# SCH_6502_copy_2025-03-02.net
KiCad netlist of a schematic drawn in EasyEDA
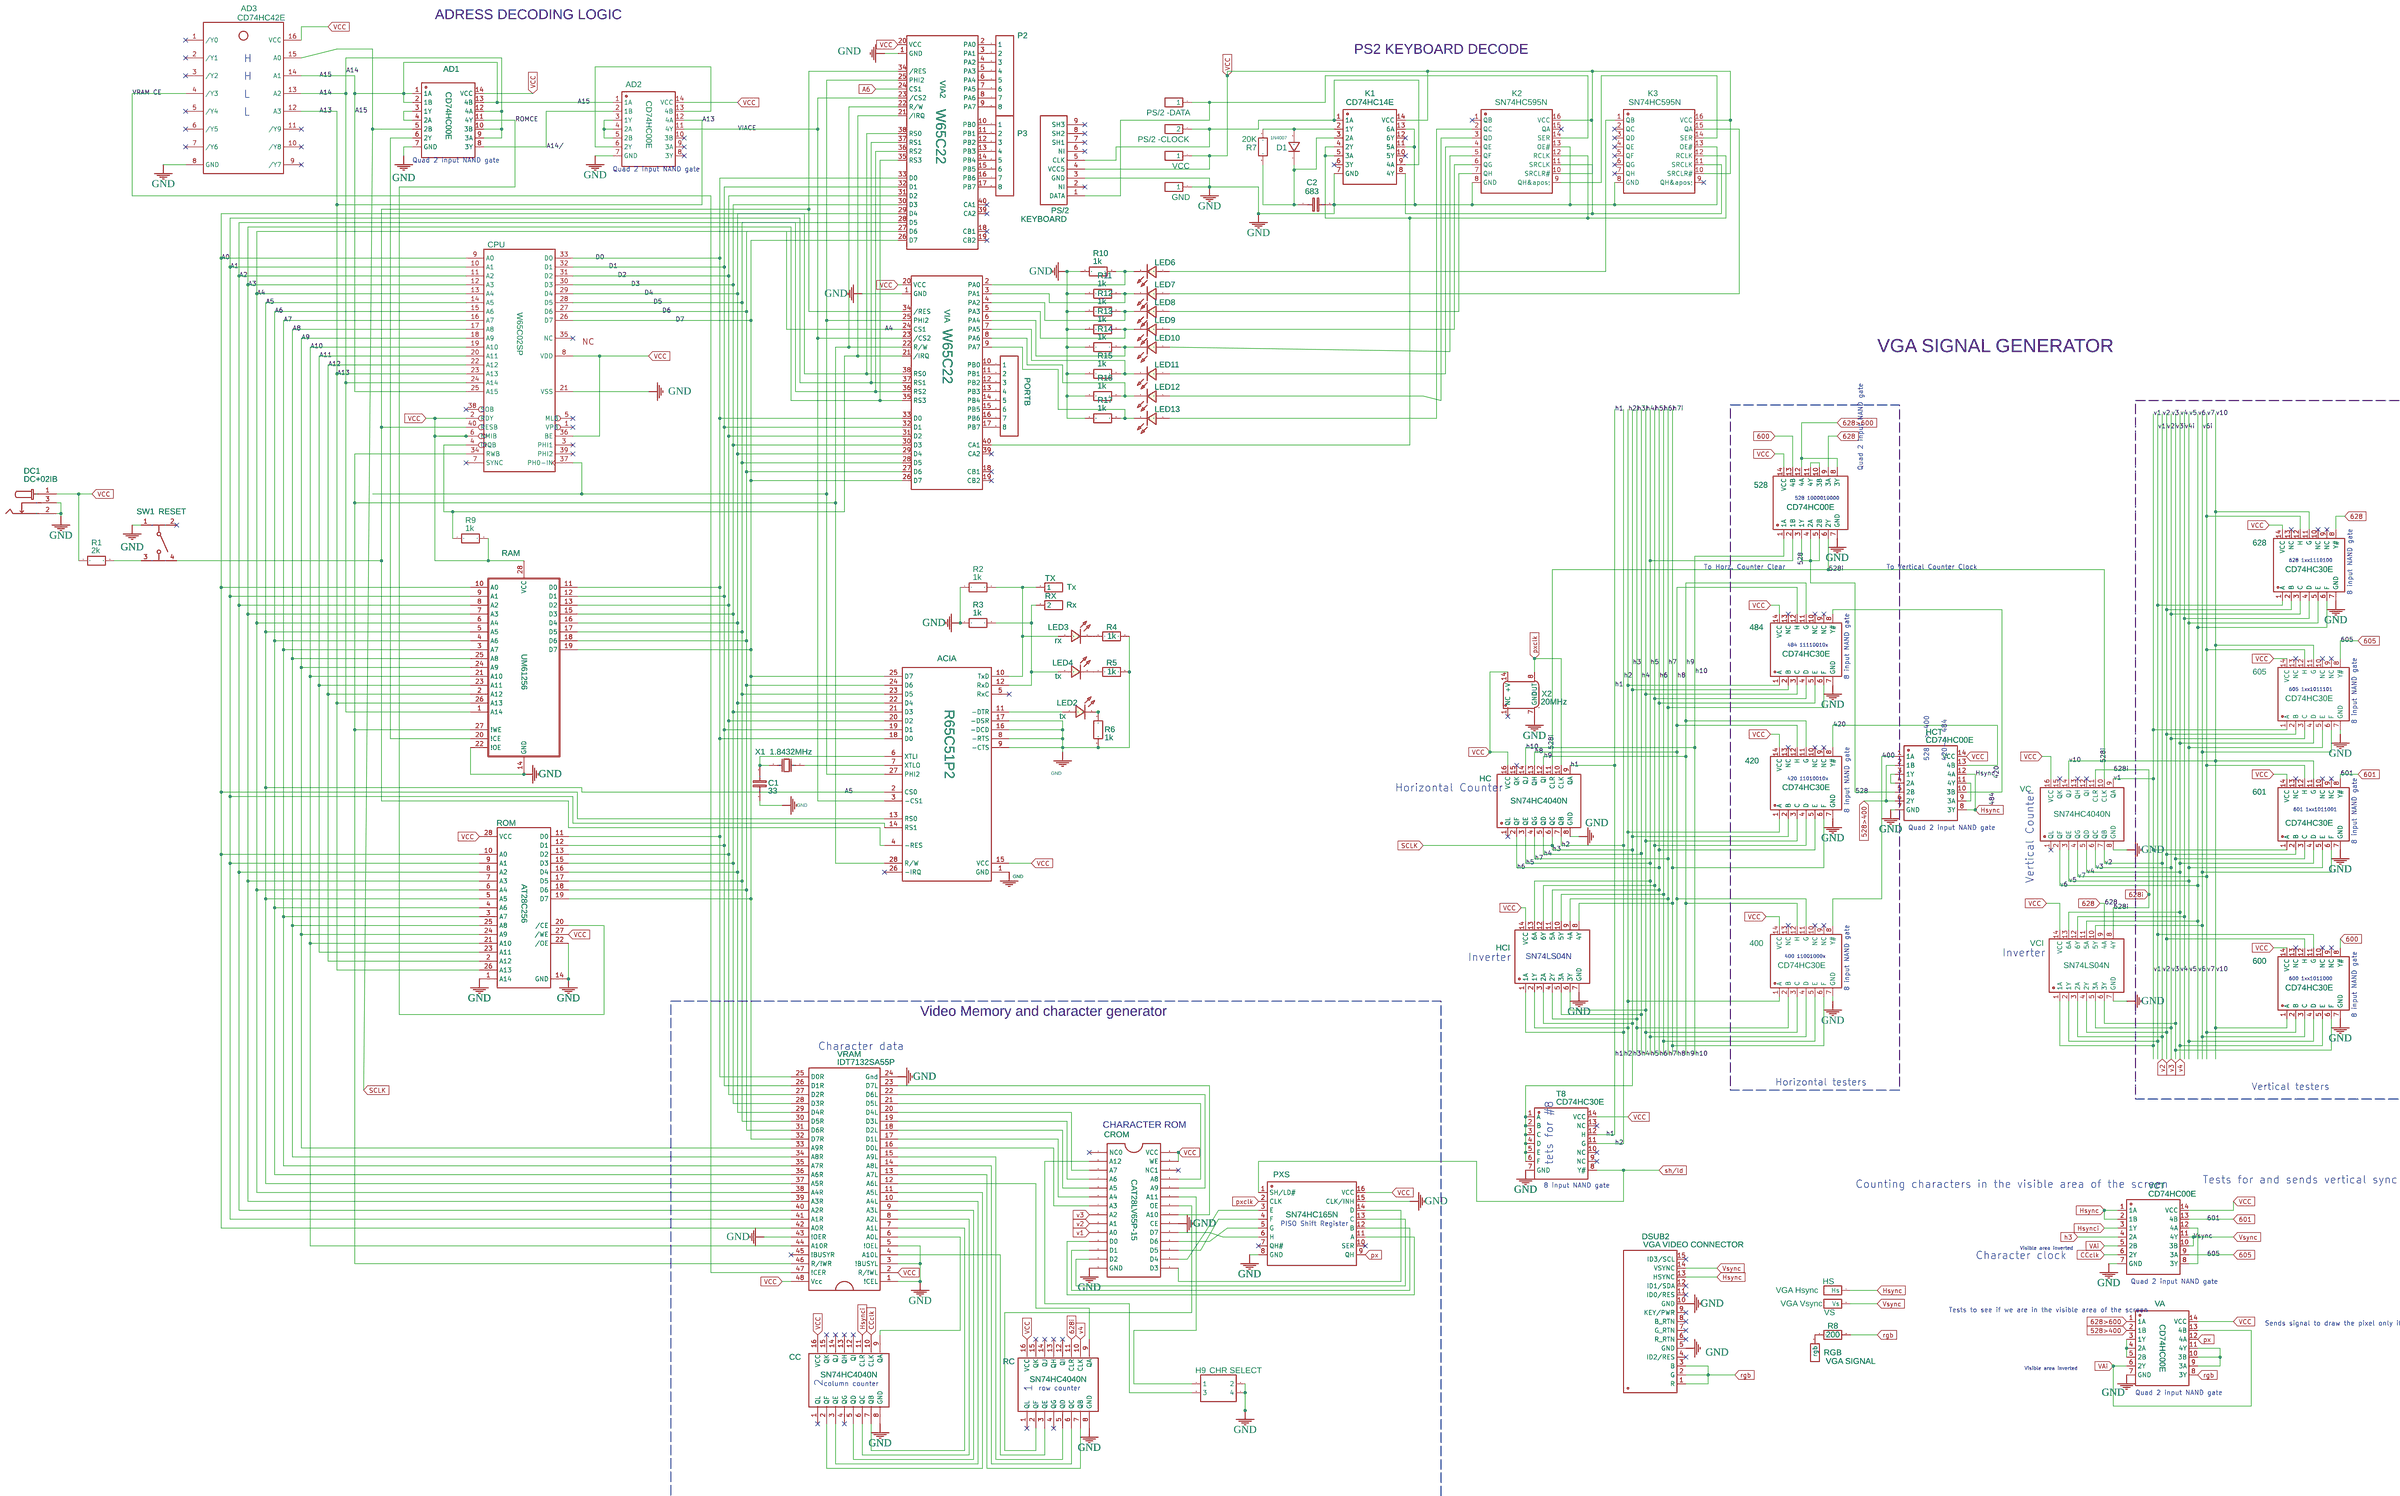
[diagram p0: schematic sheet]

(export (version "E")
  (design (tool "Eeschema 10.0.6"))
  (components
    (comp (ref "400")
      (value "CD74HC30E")
      (fields (field (name "BOM_Supplier Part") "C133818"))
      (libsource (lib "") (part "CD74HC30E"))
    )
    (comp (ref "420")
      (value "CD74HC30E")
      (fields (field (name "BOM_Supplier Part") "C133818"))
      (libsource (lib "") (part "CD74HC30E"))
    )
    (comp (ref "484")
      (value "CD74HC30E")
      (fields (field (name "BOM_Supplier Part") "C133818"))
      (libsource (lib "") (part "CD74HC30E"))
    )
    (comp (ref "528") (value "CD74HC00E") (libsource (lib "") (part "CD74HC00E_1")))
    (comp (ref "600")
      (value "CD74HC30E")
      (fields (field (name "BOM_Supplier Part") "C133818"))
      (libsource (lib "") (part "CD74HC30E"))
    )
    (comp (ref "601")
      (value "CD74HC30E")
      (fields (field (name "BOM_Supplier Part") "C133818"))
      (libsource (lib "") (part "CD74HC30E"))
    )
    (comp (ref "605")
      (value "CD74HC30E")
      (fields (field (name "BOM_Supplier Part") "C133818"))
      (libsource (lib "") (part "CD74HC30E"))
    )
    (comp (ref "628")
      (value "CD74HC30E")
      (fields (field (name "BOM_Supplier Part") "C133818"))
      (libsource (lib "") (part "CD74HC30E"))
    )
    (comp (ref "ACIA")
      (value "R65C51P2")
      (fields (field (name "BOM_Manufacturer Part") "6551 ACIA"))
      (libsource (lib "") (part "R6551_ACIA copy"))
    )
    (comp (ref "AD1") (value "CD74HC00E") (libsource (lib "") (part "CD74HC00E")))
    (comp (ref "AD2") (value "CD74HC00E") (libsource (lib "") (part "CD74HC00E")))
    (comp (ref "AD3") (value "CD74HC42E") (libsource (lib "") (part "CD74HC42E")))
    (comp (ref "C1") (value "33") (libsource (lib "") (part "C_RAD-0.2_EU")))
    (comp (ref "C2") (value "683") (libsource (lib "") (part "C_RAD-0.2_EU_1")))
    (comp (ref "CC") (value "SN74HC4040N") (libsource (lib "") (part "SN74HC4040N_3")))
    (comp (ref "CLK")
      (value "PS/2 -CLOCK")
      (fields (field (name "BOM_Supplier Part") "C81276"))
      (libsource (lib "") (part "HDR-M-2.54_1x1_2"))
    )
    (comp (ref "CPU") (value "W65C02SP") (libsource (lib "") (part "W65C02SP")))
    (comp (ref "CROM")
      (value "CAT28LV65P-15")
      (fields (field (name "BOM_Manufacturer Part") "CAT28C64AP-20"))
      (libsource (lib "") (part "CAT28C64AP-20"))
    )
    (comp (ref "D1")
      (value "1N4007")
      (fields (field (name "BOM_Supplier Part") "C106903"))
      (libsource (lib "") (part "1N4007"))
    )
    (comp (ref "DATA")
      (value "PS/2 -DATA")
      (fields (field (name "BOM_Supplier Part") "C81276"))
      (libsource (lib "") (part "HDR-M-2.54_1x1_4"))
    )
    (comp (ref "DC1")
      (value "DC+02IB")
      (fields (field (name "BOM_Supplier Part") "C718035"))
      (libsource (lib "") (part "DC+02IB"))
    )
    (comp (ref "DSUB2") (value "VGA VIDEO CONNECTOR") (libsource (lib "") (part "VGA VIDEO CONNECTOR")))
    (comp (ref "GND")
      (value "GND")
      (fields (field (name "BOM_Supplier Part") "C81276"))
      (libsource (lib "") (part "HDR-M-2.54_1x1_1"))
    )
    (comp (ref "H9")
      (value "CHR SELECT")
      (fields (field (name "BOM_Supplier Part") "C239342"))
      (libsource (lib "") (part "HDR-F-2.54_2x2"))
    )
    (comp (ref "HC") (value "SN74HC4040N") (libsource (lib "") (part "SN74HC4040N")))
    (comp (ref "HCI")
      (value "U39")
      (fields (field (name "BOM_Manufacturer Part") "SN74LS04N") (field (name "BOM_Supplier Part") "C183657"))
      (libsource (lib "") (part "SN74LS04N"))
    )
    (comp (ref "HCT") (value "CD74HC00E") (libsource (lib "") (part "CD74HC00E_2")))
    (comp (ref "HS")
      (value "VGA Hsync")
      (fields (field (name "BOM_Supplier Part") "C81276"))
      (libsource (lib "") (part "HDR-M-2.54_1x1"))
    )
    (comp (ref "K1") (value "CD74HC14E") (libsource (lib "") (part "CD74HC14E")))
    (comp (ref "K2")
      (value "SN74HC595N")
      (fields (field (name "BOM_Supplier Part") "C78711"))
      (libsource (lib "") (part "SN74HC595N"))
    )
    (comp (ref "K3")
      (value "SN74HC595N")
      (fields (field (name "BOM_Supplier Part") "C78711"))
      (libsource (lib "") (part "SN74HC595N"))
    )
    (comp (ref "KEYBOARD") (value "PS/2") (libsource (lib "") (part "PS/2")))
    (comp (ref "LED2")
      (value "tx")
      (fields
        (field (name "BOM_Manufacturer Part") "204-10SDRD/S530-A3-L")
        (field (name "BOM_Supplier Part") "C84774")
      )
      (libsource (lib "") (part "LED-TH-3mm_R_1"))
    )
    (comp (ref "LED3")
      (value "rx")
      (fields
        (field (name "BOM_Manufacturer Part") "204-10SUBC/S400-A4")
        (field (name "BOM_Supplier Part") "C86881")
      )
      (libsource (lib "") (part "LED-TH-3mm_B"))
    )
    (comp (ref "LED4")
      (value "tx")
      (fields
        (field (name "BOM_Manufacturer Part") "204-10SDRD/S530-A3-L")
        (field (name "BOM_Supplier Part") "C84774")
      )
      (libsource (lib "") (part "LED-TH-3mm_R_1"))
    )
    (comp (ref "LED6")
      (value "LED-TH-3mm_R")
      (fields
        (field (name "BOM_Manufacturer Part") "204-10SDRD/S530-A3-L")
        (field (name "BOM_Supplier Part") "C84774")
      )
      (libsource (lib "") (part "LED-TH-3mm_R"))
    )
    (comp (ref "LED7")
      (value "LED-TH-3mm_R")
      (fields
        (field (name "BOM_Manufacturer Part") "204-10SDRD/S530-A3-L")
        (field (name "BOM_Supplier Part") "C84774")
      )
      (libsource (lib "") (part "LED-TH-3mm_R"))
    )
    (comp (ref "LED8")
      (value "LED-TH-3mm_R")
      (fields
        (field (name "BOM_Manufacturer Part") "204-10SDRD/S530-A3-L")
        (field (name "BOM_Supplier Part") "C84774")
      )
      (libsource (lib "") (part "LED-TH-3mm_R"))
    )
    (comp (ref "LED9")
      (value "LED-TH-3mm_R")
      (fields
        (field (name "BOM_Manufacturer Part") "204-10SDRD/S530-A3-L")
        (field (name "BOM_Supplier Part") "C84774")
      )
      (libsource (lib "") (part "LED-TH-3mm_R"))
    )
    (comp (ref "LED10")
      (value "LED-TH-3mm_R")
      (fields
        (field (name "BOM_Manufacturer Part") "204-10SDRD/S530-A3-L")
        (field (name "BOM_Supplier Part") "C84774")
      )
      (libsource (lib "") (part "LED-TH-3mm_R"))
    )
    (comp (ref "LED11")
      (value "LED-TH-3mm_R")
      (fields
        (field (name "BOM_Manufacturer Part") "204-10SDRD/S530-A3-L")
        (field (name "BOM_Supplier Part") "C84774")
      )
      (libsource (lib "") (part "LED-TH-3mm_R"))
    )
    (comp (ref "LED12")
      (value "LED-TH-3mm_R")
      (fields
        (field (name "BOM_Manufacturer Part") "204-10SDRD/S530-A3-L")
        (field (name "BOM_Supplier Part") "C84774")
      )
      (libsource (lib "") (part "LED-TH-3mm_R"))
    )
    (comp (ref "LED13")
      (value "LED-TH-3mm_R")
      (fields
        (field (name "BOM_Manufacturer Part") "204-10SDRD/S530-A3-L")
        (field (name "BOM_Supplier Part") "C84774")
      )
      (libsource (lib "") (part "LED-TH-3mm_R"))
    )
    (comp (ref "P2")
      (value "HDR-F-2.54_1x8")
      (fields (field (name "BOM_Supplier Part") "C225505"))
      (libsource (lib "") (part "HDR-F-2.54_1x8"))
    )
    (comp (ref "P3")
      (value "P3")
      (fields (field (name "BOM_Supplier Part") "C225505"))
      (libsource (lib "") (part "HDR-F-2.54_1x8"))
    )
    (comp (ref "PORTB")
      (value "HDR-F-2.54_1x8")
      (fields (field (name "BOM_Supplier Part") "C225505"))
      (libsource (lib "") (part "HDR-F-2.54_1x8_1"))
    )
    (comp (ref "PXS")
      (value "SN74HC165N")
      (fields (field (name "BOM_Supplier Part") "C2909"))
      (libsource (lib "") (part "SN74HC165N"))
    )
    (comp (ref "R1") (value "2k") (libsource (lib "") (part "R_AXIAL-0.4_EU")))
    (comp (ref "R2") (value "1k") (libsource (lib "") (part "R_AXIAL-0.3_EU")))
    (comp (ref "R3") (value "1k") (libsource (lib "") (part "R_AXIAL-0.3_EU")))
    (comp (ref "R4") (value "1k") (libsource (lib "") (part "R_AXIAL-0.4_EU")))
    (comp (ref "R5") (value "1k") (libsource (lib "") (part "R_AXIAL-0.4_EU")))
    (comp (ref "R6") (value "1k") (libsource (lib "") (part "R_AXIAL-0.4_EU_1")))
    (comp (ref "R7") (value "20K") (libsource (lib "") (part "R_AXIAL-0.4_EU_1")))
    (comp (ref "R8") (value "200") (libsource (lib "") (part "R_AXIAL-0.4_EU")))
    (comp (ref "R9") (value "1k") (libsource (lib "") (part "R_AXIAL-0.3_EU")))
    (comp (ref "R10") (value "1k") (libsource (lib "") (part "R_AXIAL-0.4_EU")))
    (comp (ref "R11") (value "1k") (libsource (lib "") (part "R_AXIAL-0.4_EU")))
    (comp (ref "R12") (value "1k") (libsource (lib "") (part "R_AXIAL-0.4_EU")))
    (comp (ref "R13") (value "1k") (libsource (lib "") (part "R_AXIAL-0.4_EU")))
    (comp (ref "R14") (value "1k") (libsource (lib "") (part "R_AXIAL-0.4_EU")))
    (comp (ref "R15") (value "1k") (libsource (lib "") (part "R_AXIAL-0.4_EU")))
    (comp (ref "R16") (value "1k") (libsource (lib "") (part "R_AXIAL-0.4_EU")))
    (comp (ref "R17") (value "1k") (libsource (lib "") (part "R_AXIAL-0.4_EU")))
    (comp (ref "RAM") (value "UM61256") (libsource (lib "") (part "UM61256")))
    (comp (ref "RC") (value "SN74HC4040N") (libsource (lib "") (part "SN74HC4040N_2")))
    (comp (ref "RGB")
      (value "VGA SIGNAL")
      (fields (field (name "BOM_Supplier Part") "C81276"))
      (libsource (lib "") (part "HDR-M-2.54_1x1_6"))
    )
    (comp (ref "ROM") (value "AT28C256") (libsource (lib "") (part "AT28C256")))
    (comp (ref "RX")
      (value "Rx")
      (fields (field (name "BOM_Supplier Part") "C81276"))
      (libsource (lib "") (part "HDR-M-2.54_1x1_5"))
    )
    (comp (ref "SW1")
      (value "RESET")
      (fields
        (field (name "BOM_Manufacturer Part") "Switch,6*6*6Plastic head,260G, 0.25mm,Straight line")
        (field (name "BOM_Supplier Part") "C71836")
      )
      (libsource (lib "") (part "Button-6x6x6mm"))
    )
    (comp (ref "T8")
      (value "CD74HC30E")
      (fields (field (name "BOM_Supplier Part") "C133818"))
      (libsource (lib "") (part "CD74HC30E_1"))
    )
    (comp (ref "TX")
      (value "Tx")
      (fields (field (name "BOM_Supplier Part") "C81276"))
      (libsource (lib "") (part "HDR-M-2.54_1x1_8"))
    )
    (comp (ref "VA") (value "CD74HC00E") (libsource (lib "") (part "CD74HC00E_4")))
    (comp (ref "VC") (value "SN74HC4040N") (libsource (lib "") (part "SN74HC4040N_1")))
    (comp (ref "VCC")
      (value "VCC")
      (fields (field (name "BOM_Supplier Part") "C81276"))
      (libsource (lib "") (part "HDR-M-2.54_1x1_7"))
    )
    (comp (ref "VCI")
      (value "SN74LS04N")
      (fields (field (name "BOM_Supplier Part") "C183657"))
      (libsource (lib "") (part "SN74LS04N_1"))
    )
    (comp (ref "VCT") (value "CD74HC00E") (libsource (lib "") (part "CD74HC00E_3")))
    (comp (ref "VIA")
      (value "W65C22")
      (fields (field (name "BOM_Manufacturer Part") "W65C02S"))
      (libsource (lib "") (part "W65C22 VIA"))
    )
    (comp (ref "VIA2")
      (value "W65C22")
      (fields (field (name "BOM_Manufacturer Part") "W65C02S"))
      (libsource (lib "") (part "W65C22 VIA"))
    )
    (comp (ref "VRAM") (value "IDT7132SA55P") (libsource (lib "") (part "IDT7132SA55P")))
    (comp (ref "VS")
      (value "VGA Vsync")
      (fields (field (name "BOM_Supplier Part") "C81276"))
      (libsource (lib "") (part "HDR-M-2.54_1x1_3"))
    )
    (comp (ref "X1")
      (value "1.8432MHz")
      (fields
        (field (name "BOM_Manufacturer Part") "X49UD18432MSD2SC-1")
        (field (name "BOM_Supplier Part") "C2179")
      )
      (libsource (lib "") (part "X49UD18432MSD2SC-1"))
    )
    (comp (ref "X2") (value "20MHz") (libsource (lib "") (part "AXE25-50-10-4F-5.000MHz")))
  )
  (nets
    (net (code "1") (name "/400") (class "Default")
      (node (ref "400") (pin "8") (pinfunction "Y#_8") (pintype "unspecified"))
      (node (ref "HCT") (pin "1") (pinfunction "1A_1") (pintype "unspecified"))
    )
    (net (code "2") (name "/420") (class "Default")
      (node (ref "420") (pin "8") (pinfunction "Y#_8") (pintype "unspecified"))
      (node (ref "HCT") (pin "13") (pinfunction "4B_13") (pintype "unspecified"))
    )
    (net (code "3") (name "/484") (class "Default")
      (node (ref "484") (pin "8") (pinfunction "Y#_8") (pintype "unspecified"))
      (node (ref "HCT") (pin "10") (pinfunction "3B_10") (pintype "unspecified"))
    )
    (net (code "4") (name "/528") (class "Default")
      (node (ref "528") (pin "3") (pinfunction "1Y_3") (pintype "unspecified"))
      (node (ref "528") (pin "4") (pinfunction "2A_4") (pintype "unspecified"))
      (node (ref "528") (pin "5") (pinfunction "2B_5") (pintype "unspecified"))
      (node (ref "HCT") (pin "5") (pinfunction "2B_5") (pintype "unspecified"))
    )
    (net (code "5") (name "/528i") (class "Default")
      (node (ref "528") (pin "6") (pinfunction "2Y_6") (pintype "unspecified"))
      (node (ref "HC") (pin "11") (pinfunction "CLR_11") (pintype "unspecified"))
      (node (ref "VC") (pin "10") (pinfunction "CLK_10") (pintype "unspecified"))
    )
    (net (code "6") (name "/A0") (class "Default")
      (node (ref "ACIA") (pin "13") (pinfunction "RS0_13") (pintype "unspecified"))
      (node (ref "CPU") (pin "9") (pinfunction "A0_9") (pintype "unspecified"))
      (node (ref "RAM") (pin "10") (pinfunction "A0_10") (pintype "input"))
      (node (ref "ROM") (pin "10") (pinfunction "A0_10") (pintype "input"))
      (node (ref "VIA") (pin "38") (pinfunction "RS0_38") (pintype "unspecified"))
      (node (ref "VIA2") (pin "38") (pinfunction "RS0_38") (pintype "unspecified"))
      (node (ref "VRAM") (pin "42") (pinfunction "A0R_42") (pintype "unspecified"))
    )
    (net (code "7") (name "/A1") (class "Default")
      (node (ref "ACIA") (pin "14") (pinfunction "RS1_14") (pintype "unspecified"))
      (node (ref "CPU") (pin "10") (pinfunction "A1_10") (pintype "unspecified"))
      (node (ref "RAM") (pin "9") (pinfunction "A1_9") (pintype "input"))
      (node (ref "ROM") (pin "9") (pinfunction "A1_9") (pintype "input"))
      (node (ref "VIA") (pin "37") (pinfunction "RS1_37") (pintype "unspecified"))
      (node (ref "VIA2") (pin "37") (pinfunction "RS1_37") (pintype "unspecified"))
      (node (ref "VRAM") (pin "41") (pinfunction "A1R_41") (pintype "unspecified"))
    )
    (net (code "8") (name "/A2") (class "Default")
      (node (ref "CPU") (pin "11") (pinfunction "A2_11") (pintype "unspecified"))
      (node (ref "RAM") (pin "8") (pinfunction "A2_8") (pintype "input"))
      (node (ref "ROM") (pin "8") (pinfunction "A2_8") (pintype "input"))
      (node (ref "VIA") (pin "36") (pinfunction "RS2_36") (pintype "unspecified"))
      (node (ref "VIA2") (pin "36") (pinfunction "RS2_36") (pintype "unspecified"))
      (node (ref "VRAM") (pin "40") (pinfunction "A2R_40") (pintype "unspecified"))
    )
    (net (code "9") (name "/A3") (class "Default")
      (node (ref "CPU") (pin "12") (pinfunction "A3_12") (pintype "unspecified"))
      (node (ref "RAM") (pin "7") (pinfunction "A3_7") (pintype "input"))
      (node (ref "ROM") (pin "7") (pinfunction "A3_7") (pintype "input"))
      (node (ref "VIA") (pin "35") (pinfunction "RS3_35") (pintype "unspecified"))
      (node (ref "VIA2") (pin "35") (pinfunction "RS3_35") (pintype "unspecified"))
      (node (ref "VRAM") (pin "39") (pinfunction "A3R_39") (pintype "unspecified"))
    )
    (net (code "10") (name "/A4") (class "Default")
      (node (ref "CPU") (pin "13") (pinfunction "A4_13") (pintype "unspecified"))
      (node (ref "RAM") (pin "6") (pinfunction "A4_6") (pintype "input"))
      (node (ref "ROM") (pin "6") (pinfunction "A4_6") (pintype "input"))
      (node (ref "VIA") (pin "24") (pinfunction "CS1_24") (pintype "unspecified"))
      (node (ref "VRAM") (pin "38") (pinfunction "A4R_38") (pintype "unspecified"))
    )
    (net (code "11") (name "/A5") (class "Default")
      (node (ref "ACIA") (pin "2") (pinfunction "CS0_2") (pintype "unspecified"))
      (node (ref "CPU") (pin "14") (pinfunction "A5_14") (pintype "unspecified"))
      (node (ref "RAM") (pin "5") (pinfunction "A5_5") (pintype "input"))
      (node (ref "ROM") (pin "5") (pinfunction "A5_5") (pintype "input"))
      (node (ref "VRAM") (pin "37") (pinfunction "A5R_37") (pintype "unspecified"))
    )
    (net (code "12") (name "/A7") (class "Default")
      (node (ref "CPU") (pin "16") (pinfunction "A7_16") (pintype "unspecified"))
      (node (ref "RAM") (pin "3") (pinfunction "A7_3") (pintype "input"))
      (node (ref "ROM") (pin "3") (pinfunction "A7_3") (pintype "input"))
      (node (ref "VRAM") (pin "35") (pinfunction "A7R_35") (pintype "unspecified"))
    )
    (net (code "13") (name "/A8") (class "Default")
      (node (ref "CPU") (pin "17") (pinfunction "A8_17") (pintype "unspecified"))
      (node (ref "RAM") (pin "25") (pinfunction "A8_25") (pintype "input"))
      (node (ref "ROM") (pin "25") (pinfunction "A8_25") (pintype "input"))
      (node (ref "VRAM") (pin "34") (pinfunction "A8R_34") (pintype "unspecified"))
    )
    (net (code "14") (name "/A9") (class "Default")
      (node (ref "CPU") (pin "18") (pinfunction "A9_18") (pintype "unspecified"))
      (node (ref "RAM") (pin "24") (pinfunction "A9_24") (pintype "input"))
      (node (ref "ROM") (pin "24") (pinfunction "A9_24") (pintype "input"))
      (node (ref "VRAM") (pin "33") (pinfunction "A9R_33") (pintype "unspecified"))
    )
    (net (code "15") (name "/A10") (class "Default")
      (node (ref "CPU") (pin "19") (pinfunction "A10_19") (pintype "unspecified"))
      (node (ref "RAM") (pin "21") (pinfunction "A10_21") (pintype "input"))
      (node (ref "ROM") (pin "21") (pinfunction "A10_21") (pintype "input"))
      (node (ref "VRAM") (pin "44") (pinfunction "A10R_44") (pintype "unspecified"))
    )
    (net (code "16") (name "/A11") (class "Default")
      (node (ref "CPU") (pin "20") (pinfunction "A11_20") (pintype "unspecified"))
      (node (ref "RAM") (pin "23") (pinfunction "A11_23") (pintype "input"))
      (node (ref "ROM") (pin "23") (pinfunction "A11_23") (pintype "input"))
    )
    (net (code "17") (name "/A12") (class "Default")
      (node (ref "CPU") (pin "22") (pinfunction "A12_22") (pintype "unspecified"))
      (node (ref "RAM") (pin "2") (pinfunction "A12_2") (pintype "input"))
      (node (ref "ROM") (pin "2") (pinfunction "A12_2") (pintype "input"))
    )
    (net (code "18") (name "/A13") (class "Default")
      (node (ref "AD2") (pin "12") (pinfunction "4A_12") (pintype "unspecified"))
      (node (ref "AD3") (pin "12") (pinfunction "A3_12") (pintype "unspecified"))
      (node (ref "CPU") (pin "23") (pinfunction "A13_23") (pintype "unspecified"))
      (node (ref "RAM") (pin "26") (pinfunction "A13_26") (pintype "input"))
      (node (ref "ROM") (pin "26") (pinfunction "A13_26") (pintype "input"))
    )
    (net (code "19") (name "/A14") (class "Default")
      (node (ref "AD1") (pin "10") (pinfunction "3B_10") (pintype "unspecified"))
      (node (ref "AD1") (pin "12") (pinfunction "4A_12") (pintype "unspecified"))
      (node (ref "AD1") (pin "9") (pinfunction "3A_9") (pintype "unspecified"))
      (node (ref "AD3") (pin "13") (pinfunction "A2_13") (pintype "unspecified"))
      (node (ref "CPU") (pin "24") (pinfunction "A14_24") (pintype "unspecified"))
      (node (ref "RAM") (pin "1") (pinfunction "A14_1") (pintype "input"))
    )
    (net (code "20") (name "/A14{slash}") (class "Default")
      (node (ref "AD1") (pin "8") (pinfunction "3Y_8") (pintype "unspecified"))
      (node (ref "AD2") (pin "2") (pinfunction "1B_2") (pintype "unspecified"))
    )
    (net (code "21") (name "/A15") (class "Default")
      (node (ref "AD1") (pin "1") (pinfunction "1A_1") (pintype "unspecified"))
      (node (ref "AD1") (pin "13") (pinfunction "4B_13") (pintype "unspecified"))
      (node (ref "AD1") (pin "2") (pinfunction "1B_2") (pintype "unspecified"))
      (node (ref "AD2") (pin "1") (pinfunction "1A_1") (pintype "unspecified"))
      (node (ref "AD3") (pin "14") (pinfunction "A1_14") (pintype "unspecified"))
      (node (ref "CPU") (pin "25") (pinfunction "A15_25") (pintype "unspecified"))
    )
    (net (code "22") (name "/D0") (class "Default")
      (node (ref "ACIA") (pin "18") (pinfunction "D0_18") (pintype "unspecified"))
      (node (ref "CPU") (pin "33") (pinfunction "D0_33") (pintype "unspecified"))
      (node (ref "RAM") (pin "11") (pinfunction "D0_11") (pintype "unspecified"))
      (node (ref "ROM") (pin "11") (pinfunction "D0_11") (pintype "bidirectional"))
      (node (ref "VIA") (pin "33") (pinfunction "D0_33") (pintype "unspecified"))
      (node (ref "VIA2") (pin "33") (pinfunction "D0_33") (pintype "unspecified"))
      (node (ref "VRAM") (pin "25") (pinfunction "D0R_25") (pintype "unspecified"))
    )
    (net (code "23") (name "/D1") (class "Default")
      (node (ref "ACIA") (pin "19") (pinfunction "D1_19") (pintype "unspecified"))
      (node (ref "CPU") (pin "32") (pinfunction "D1_32") (pintype "unspecified"))
      (node (ref "RAM") (pin "12") (pinfunction "D1_12") (pintype "unspecified"))
      (node (ref "ROM") (pin "12") (pinfunction "D1_12") (pintype "bidirectional"))
      (node (ref "VIA") (pin "32") (pinfunction "D1_32") (pintype "unspecified"))
      (node (ref "VIA2") (pin "32") (pinfunction "D1_32") (pintype "unspecified"))
      (node (ref "VRAM") (pin "26") (pinfunction "D1R_26") (pintype "unspecified"))
    )
    (net (code "24") (name "/D2") (class "Default")
      (node (ref "ACIA") (pin "20") (pinfunction "D2_20") (pintype "unspecified"))
      (node (ref "CPU") (pin "31") (pinfunction "D2_31") (pintype "unspecified"))
      (node (ref "RAM") (pin "13") (pinfunction "D2_13") (pintype "unspecified"))
      (node (ref "ROM") (pin "13") (pinfunction "D2_13") (pintype "bidirectional"))
      (node (ref "VIA") (pin "31") (pinfunction "D2_31") (pintype "unspecified"))
      (node (ref "VIA2") (pin "31") (pinfunction "D2_31") (pintype "unspecified"))
      (node (ref "VRAM") (pin "27") (pinfunction "D2R_27") (pintype "unspecified"))
    )
    (net (code "25") (name "/D3") (class "Default")
      (node (ref "ACIA") (pin "21") (pinfunction "D3_21") (pintype "unspecified"))
      (node (ref "CPU") (pin "30") (pinfunction "D3_30") (pintype "unspecified"))
      (node (ref "RAM") (pin "15") (pinfunction "D3_15") (pintype "unspecified"))
      (node (ref "ROM") (pin "15") (pinfunction "D3_15") (pintype "bidirectional"))
      (node (ref "VIA") (pin "30") (pinfunction "D3_30") (pintype "unspecified"))
      (node (ref "VIA2") (pin "30") (pinfunction "D3_30") (pintype "unspecified"))
      (node (ref "VRAM") (pin "28") (pinfunction "D3R_28") (pintype "unspecified"))
    )
    (net (code "26") (name "/D4") (class "Default")
      (node (ref "ACIA") (pin "22") (pinfunction "D4_22") (pintype "unspecified"))
      (node (ref "CPU") (pin "29") (pinfunction "D4_29") (pintype "unspecified"))
      (node (ref "RAM") (pin "16") (pinfunction "D4_16") (pintype "unspecified"))
      (node (ref "ROM") (pin "16") (pinfunction "D4_16") (pintype "bidirectional"))
      (node (ref "VIA") (pin "29") (pinfunction "D4_29") (pintype "unspecified"))
      (node (ref "VIA2") (pin "29") (pinfunction "D4_29") (pintype "unspecified"))
      (node (ref "VRAM") (pin "29") (pinfunction "D4R_29") (pintype "unspecified"))
    )
    (net (code "27") (name "/D5") (class "Default")
      (node (ref "ACIA") (pin "23") (pinfunction "D5_23") (pintype "unspecified"))
      (node (ref "CPU") (pin "28") (pinfunction "D5_28") (pintype "unspecified"))
      (node (ref "RAM") (pin "17") (pinfunction "D5_17") (pintype "unspecified"))
      (node (ref "ROM") (pin "17") (pinfunction "D5_17") (pintype "bidirectional"))
      (node (ref "VIA") (pin "28") (pinfunction "D5_28") (pintype "unspecified"))
      (node (ref "VIA2") (pin "28") (pinfunction "D5_28") (pintype "unspecified"))
      (node (ref "VRAM") (pin "30") (pinfunction "D5R_30") (pintype "unspecified"))
    )
    (net (code "28") (name "/D6") (class "Default")
      (node (ref "ACIA") (pin "24") (pinfunction "D6_24") (pintype "unspecified"))
      (node (ref "CPU") (pin "27") (pinfunction "D6_27") (pintype "unspecified"))
      (node (ref "RAM") (pin "18") (pinfunction "D6_18") (pintype "unspecified"))
      (node (ref "ROM") (pin "18") (pinfunction "D6_18") (pintype "bidirectional"))
      (node (ref "VIA") (pin "27") (pinfunction "D6_27") (pintype "unspecified"))
      (node (ref "VIA2") (pin "27") (pinfunction "D6_27") (pintype "unspecified"))
      (node (ref "VRAM") (pin "31") (pinfunction "D6R_31") (pintype "unspecified"))
    )
    (net (code "29") (name "/D7") (class "Default")
      (node (ref "ACIA") (pin "25") (pinfunction "D7_25") (pintype "unspecified"))
      (node (ref "CPU") (pin "26") (pinfunction "D7_26") (pintype "unspecified"))
      (node (ref "RAM") (pin "19") (pinfunction "D7_19") (pintype "unspecified"))
      (node (ref "ROM") (pin "19") (pinfunction "D7_19") (pintype "bidirectional"))
      (node (ref "VIA") (pin "26") (pinfunction "D7_26") (pintype "unspecified"))
      (node (ref "VIA2") (pin "26") (pinfunction "D7_26") (pintype "unspecified"))
      (node (ref "VRAM") (pin "32") (pinfunction "D7R_32") (pintype "unspecified"))
    )
    (net (code "30") (name "/ROMCE") (class "Default")
      (node (ref "AD1") (pin "11") (pinfunction "4Y_11") (pintype "unspecified"))
      (node (ref "ROM") (pin "20") (pinfunction "/CE_20") (pintype "input"))
    )
    (net (code "31") (name "/VIACE") (class "Default")
      (node (ref "ACIA") (pin "3") (pinfunction "-CS1_3") (pintype "unspecified"))
      (node (ref "AD2") (pin "11") (pinfunction "4Y_11") (pintype "unspecified"))
      (node (ref "VIA") (pin "23") (pinfunction "/CS2_23") (pintype "unspecified"))
      (node (ref "VIA2") (pin "23") (pinfunction "/CS2_23") (pintype "unspecified"))
    )
    (net (code "32") (name "/VRAM CE") (class "Default")
      (node (ref "AD3") (pin "4") (pinfunction "/Y3_4") (pintype "unspecified"))
      (node (ref "VRAM") (pin "47") (pinfunction "!CER_47") (pintype "unspecified"))
    )
    (net (code "33") (name "/h1") (class "Default")
      (node (ref "HC") (pin "9") (pinfunction "QA_9") (pintype "unspecified"))
      (node (ref "T8") (pin "12") (pinfunction "H_12") (pintype "unspecified"))
    )
    (net (code "34") (name "/h2") (class "Default")
      (node (ref "HC") (pin "7") (pinfunction "QB_7") (pintype "unspecified"))
      (node (ref "HCI") (pin "1") (pinfunction "1A_1") (pintype "unspecified"))
      (node (ref "T8") (pin "11") (pinfunction "G_11") (pintype "unspecified"))
    )
    (net (code "35") (name "/h2i") (class "Default")
      (node (ref "400") (pin "1") (pinfunction "A_1") (pintype "unspecified"))
      (node (ref "420") (pin "1") (pinfunction "A_1") (pintype "unspecified"))
      (node (ref "484") (pin "1") (pinfunction "A_1") (pintype "unspecified"))
      (node (ref "HCI") (pin "2") (pinfunction "1Y_2") (pintype "unspecified"))
    )
    (net (code "36") (name "/h3i") (class "Default")
      (node (ref "400") (pin "2") (pinfunction "B_2") (pintype "unspecified"))
      (node (ref "HCI") (pin "4") (pinfunction "2Y_4") (pintype "unspecified"))
    )
    (net (code "37") (name "/h4") (class "Default")
      (node (ref "HC") (pin "5") (pinfunction "QD_5") (pintype "unspecified"))
      (node (ref "HCI") (pin "5") (pinfunction "3A_5") (pintype "unspecified"))
    )
    (net (code "38") (name "/h4i") (class "Default")
      (node (ref "400") (pin "3") (pinfunction "C_3") (pintype "unspecified"))
      (node (ref "420") (pin "3") (pinfunction "C_3") (pintype "unspecified"))
      (node (ref "484") (pin "3") (pinfunction "C_3") (pintype "unspecified"))
      (node (ref "HCI") (pin "6") (pinfunction "3Y_6") (pintype "unspecified"))
    )
    (net (code "39") (name "/h5") (class "Default")
      (node (ref "400") (pin "4") (pinfunction "D_4") (pintype "unspecified"))
      (node (ref "528") (pin "2") (pinfunction "1B_2") (pintype "unspecified"))
      (node (ref "HC") (pin "3") (pinfunction "QE_3") (pintype "unspecified"))
      (node (ref "HCI") (pin "13") (pinfunction "6A_13") (pintype "unspecified"))
    )
    (net (code "40") (name "/h5i") (class "Default")
      (node (ref "420") (pin "4") (pinfunction "D_4") (pintype "unspecified"))
      (node (ref "484") (pin "4") (pinfunction "D_4") (pintype "unspecified"))
      (node (ref "HCI") (pin "12") (pinfunction "6Y_12") (pintype "unspecified"))
    )
    (net (code "41") (name "/h6") (class "Default")
      (node (ref "420") (pin "5") (pinfunction "E_5") (pintype "unspecified"))
      (node (ref "484") (pin "5") (pinfunction "E_5") (pintype "unspecified"))
      (node (ref "HC") (pin "2") (pinfunction "QF_2") (pintype "unspecified"))
      (node (ref "HCI") (pin "11") (pinfunction "5A_11") (pintype "unspecified"))
    )
    (net (code "42") (name "/h6i") (class "Default")
      (node (ref "400") (pin "5") (pinfunction "E_5") (pintype "unspecified"))
      (node (ref "HCI") (pin "10") (pinfunction "5Y_10") (pintype "unspecified"))
    )
    (net (code "43") (name "/h7") (class "Default")
      (node (ref "484") (pin "6") (pinfunction "F_6") (pintype "unspecified"))
      (node (ref "HC") (pin "4") (pinfunction "QG_4") (pintype "unspecified"))
      (node (ref "HCI") (pin "9") (pinfunction "4A_9") (pintype "unspecified"))
    )
    (net (code "44") (name "/h7i") (class "Default")
      (node (ref "400") (pin "6") (pinfunction "F_6") (pintype "unspecified"))
      (node (ref "420") (pin "6") (pinfunction "F_6") (pintype "unspecified"))
      (node (ref "HCI") (pin "8") (pinfunction "4Y_8") (pintype "unspecified"))
    )
    (net (code "45") (name "/h8") (class "Default")
      (node (ref "400") (pin "11") (pinfunction "G_11") (pintype "unspecified"))
      (node (ref "420") (pin "12") (pinfunction "H_12") (pintype "unspecified"))
      (node (ref "484") (pin "12") (pinfunction "H_12") (pintype "unspecified"))
      (node (ref "HC") (pin "13") (pinfunction "QH_13") (pintype "unspecified"))
    )
    (net (code "46") (name "/h9") (class "Default")
      (node (ref "400") (pin "12") (pinfunction "H_12") (pintype "unspecified"))
      (node (ref "420") (pin "11") (pinfunction "G_11") (pintype "unspecified"))
      (node (ref "484") (pin "11") (pinfunction "G_11") (pintype "unspecified"))
      (node (ref "HC") (pin "12") (pinfunction "QI_12") (pintype "unspecified"))
    )
    (net (code "47") (name "/h10") (class "Default")
      (node (ref "528") (pin "1") (pinfunction "1A_1") (pintype "unspecified"))
      (node (ref "HC") (pin "14") (pinfunction "QJ_14") (pintype "unspecified"))
    )
    (net (code "48") (name "/v1i") (class "Default")
      (node (ref "600") (pin "11") (pinfunction "G_11") (pintype "unspecified"))
      (node (ref "628") (pin "1") (pinfunction "A_1") (pintype "unspecified"))
      (node (ref "VCI") (pin "2") (pinfunction "1Y_2") (pintype "unspecified"))
    )
    (net (code "49") (name "/v2i") (class "Default")
      (node (ref "600") (pin "12") (pinfunction "H_12") (pintype "unspecified"))
      (node (ref "601") (pin "2") (pinfunction "B_2") (pintype "unspecified"))
      (node (ref "605") (pin "2") (pinfunction "B_2") (pintype "unspecified"))
      (node (ref "628") (pin "2") (pinfunction "B_2") (pintype "unspecified"))
      (node (ref "VCI") (pin "4") (pinfunction "2Y_4") (pintype "unspecified"))
    )
    (net (code "50") (name "/v3i") (class "Default")
      (node (ref "600") (pin "6") (pinfunction "F_6") (pintype "unspecified"))
      (node (ref "601") (pin "3") (pinfunction "C_3") (pintype "unspecified"))
      (node (ref "VCI") (pin "6") (pinfunction "3Y_6") (pintype "unspecified"))
    )
    (net (code "51") (name "/v4i") (class "Default")
      (node (ref "628") (pin "4") (pinfunction "D_4") (pintype "unspecified"))
      (node (ref "VCI") (pin "12") (pinfunction "6Y_12") (pintype "unspecified"))
    )
    (net (code "52") (name "/v5") (class "Default")
      (node (ref "600") (pin "4") (pinfunction "D_4") (pintype "unspecified"))
      (node (ref "601") (pin "5") (pinfunction "E_5") (pintype "unspecified"))
      (node (ref "605") (pin "5") (pinfunction "E_5") (pintype "unspecified"))
      (node (ref "628") (pin "5") (pinfunction "E_5") (pintype "unspecified"))
      (node (ref "VC") (pin "3") (pinfunction "QE_3") (pintype "unspecified"))
    )
    (net (code "53") (name "/v6") (class "Default")
      (node (ref "628") (pin "6") (pinfunction "F_6") (pintype "unspecified"))
      (node (ref "VC") (pin "2") (pinfunction "QF_2") (pintype "unspecified"))
      (node (ref "VCI") (pin "11") (pinfunction "5A_11") (pintype "unspecified"))
    )
    (net (code "54") (name "/v6i") (class "Default")
      (node (ref "600") (pin "3") (pinfunction "C_3") (pintype "unspecified"))
      (node (ref "601") (pin "6") (pinfunction "F_6") (pintype "unspecified"))
      (node (ref "605") (pin "6") (pinfunction "F_6") (pintype "unspecified"))
      (node (ref "VCI") (pin "10") (pinfunction "5Y_10") (pintype "unspecified"))
    )
    (net (code "55") (name "/v7") (class "Default")
      (node (ref "600") (pin "2") (pinfunction "B_2") (pintype "unspecified"))
      (node (ref "601") (pin "12") (pinfunction "H_12") (pintype "unspecified"))
      (node (ref "605") (pin "12") (pinfunction "H_12") (pintype "unspecified"))
      (node (ref "628") (pin "12") (pinfunction "H_12") (pintype "unspecified"))
      (node (ref "VC") (pin "4") (pinfunction "QG_4") (pintype "unspecified"))
    )
    (net (code "56") (name "/v10") (class "Default")
      (node (ref "600") (pin "1") (pinfunction "A_1") (pintype "unspecified"))
      (node (ref "601") (pin "11") (pinfunction "G_11") (pintype "unspecified"))
      (node (ref "605") (pin "11") (pinfunction "G_11") (pintype "unspecified"))
      (node (ref "628") (pin "11") (pinfunction "G_11") (pintype "unspecified"))
      (node (ref "VC") (pin "14") (pinfunction "QJ_14") (pintype "unspecified"))
    )
    (net (code "57") (name "528>400") (class "Default")
      (node (ref "HCT") (pin "2") (pinfunction "1B_2") (pintype "unspecified"))
      (node (ref "HCT") (pin "6") (pinfunction "2Y_6") (pintype "unspecified"))
      (node (ref "VA") (pin "2") (pinfunction "1B_2") (pintype "unspecified"))
    )
    (net (code "58") (name "600") (class "Default")
      (node (ref "528") (pin "13") (pinfunction "4B_13") (pintype "unspecified"))
      (node (ref "600") (pin "8") (pinfunction "Y#_8") (pintype "unspecified"))
    )
    (net (code "59") (name "601") (class "Default")
      (node (ref "601") (pin "8") (pinfunction "Y#_8") (pintype "unspecified"))
      (node (ref "VCT") (pin "13") (pinfunction "4B_13") (pintype "unspecified"))
    )
    (net (code "60") (name "605") (class "Default")
      (node (ref "605") (pin "8") (pinfunction "Y#_8") (pintype "unspecified"))
      (node (ref "VCT") (pin "9") (pinfunction "3A_9") (pintype "unspecified"))
    )
    (net (code "61") (name "628") (class "Default")
      (node (ref "528") (pin "9") (pinfunction "3A_9") (pintype "unspecified"))
      (node (ref "628") (pin "8") (pinfunction "Y#_8") (pintype "unspecified"))
      (node (ref "VCI") (pin "9") (pinfunction "4A_9") (pintype "unspecified"))
    )
    (net (code "62") (name "628>600") (class "Default")
      (node (ref "528") (pin "12") (pinfunction "4A_12") (pintype "unspecified"))
      (node (ref "528") (pin "8") (pinfunction "3Y_8") (pintype "unspecified"))
      (node (ref "VA") (pin "1") (pinfunction "1A_1") (pintype "unspecified"))
    )
    (net (code "63") (name "628i") (class "Default")
      (node (ref "RC") (pin "11") (pinfunction "CLR_11") (pintype "bidirectional"))
      (node (ref "VC") (pin "11") (pinfunction "CLR_11") (pintype "unspecified"))
      (node (ref "VCI") (pin "8") (pinfunction "4Y_8") (pintype "unspecified"))
    )
    (net (code "64") (name "A6") (class "Default")
      (node (ref "CPU") (pin "15") (pinfunction "A6_15") (pintype "unspecified"))
      (node (ref "RAM") (pin "4") (pinfunction "A6_4") (pintype "input"))
      (node (ref "ROM") (pin "4") (pinfunction "A6_4") (pintype "input"))
      (node (ref "VIA2") (pin "24") (pinfunction "CS1_24") (pintype "unspecified"))
      (node (ref "VRAM") (pin "36") (pinfunction "A6R_36") (pintype "unspecified"))
    )
    (net (code "65") (name "CCclk") (class "Default")
      (node (ref "CC") (pin "10") (pinfunction "CLK_10") (pintype "bidirectional"))
      (node (ref "VCT") (pin "6") (pinfunction "2Y_6") (pintype "unspecified"))
    )
    (net (code "66") (name "GND") (class "Default")
      (node (ref "400") (pin "7") (pinfunction "GND_7") (pintype "unspecified"))
      (node (ref "420") (pin "7") (pinfunction "GND_7") (pintype "unspecified"))
      (node (ref "484") (pin "7") (pinfunction "GND_7") (pintype "unspecified"))
      (node (ref "528") (pin "7") (pinfunction "GND_7") (pintype "unspecified"))
      (node (ref "600") (pin "7") (pinfunction "GND_7") (pintype "unspecified"))
      (node (ref "601") (pin "7") (pinfunction "GND_7") (pintype "unspecified"))
      (node (ref "605") (pin "7") (pinfunction "GND_7") (pintype "unspecified"))
      (node (ref "628") (pin "7") (pinfunction "GND_7") (pintype "unspecified"))
      (node (ref "ACIA") (pin "1") (pinfunction "GND_1") (pintype "unspecified"))
      (node (ref "ACIA") (pin "16") (pinfunction "-DCD_16") (pintype "unspecified"))
      (node (ref "ACIA") (pin "17") (pinfunction "-DSR_17") (pintype "unspecified"))
      (node (ref "ACIA") (pin "8") (pinfunction "-RTS_8") (pintype "unspecified"))
      (node (ref "ACIA") (pin "9") (pinfunction "-CTS_9") (pintype "unspecified"))
      (node (ref "AD1") (pin "7") (pinfunction "GND_7") (pintype "unspecified"))
      (node (ref "AD2") (pin "7") (pinfunction "GND_7") (pintype "unspecified"))
      (node (ref "AD3") (pin "8") (pinfunction "GND_8") (pintype "unspecified"))
      (node (ref "C1") (pin "1") (pinfunction "1_1") (pintype "unspecified"))
      (node (ref "C2") (pin "2") (pinfunction "2_2") (pintype "unspecified"))
      (node (ref "CC") (pin "8") (pinfunction "GND_8") (pintype "bidirectional"))
      (node (ref "CPU") (pin "21") (pinfunction "VSS_21") (pintype "unspecified"))
      (node (ref "CROM") (pin "14") (pinfunction "GND_14") (pintype "unspecified"))
      (node (ref "CROM") (pin "20") (pinfunction "CE_20") (pintype "unspecified"))
      (node (ref "DC1") (pin "2") (pinfunction "2_2") (pintype "unspecified"))
      (node (ref "DC1") (pin "3") (pinfunction "3_3") (pintype "unspecified"))
      (node (ref "DSUB2") (pin "10") (pinfunction "GND_10") (pintype "unspecified"))
      (node (ref "DSUB2") (pin "5") (pinfunction "GND_5") (pintype "unspecified"))
      (node (ref "GND") (pin "1") (pinfunction "1_1") (pintype "input"))
      (node (ref "H9") (pin "2") (pinfunction "2_2") (pintype "unspecified"))
      (node (ref "H9") (pin "4") (pinfunction "4_4") (pintype "unspecified"))
      (node (ref "HC") (pin "8") (pinfunction "GND_8") (pintype "unspecified"))
      (node (ref "HCI") (pin "7") (pinfunction "GND_7") (pintype "unspecified"))
      (node (ref "HCT") (pin "7") (pinfunction "GND_7") (pintype "unspecified"))
      (node (ref "K1") (pin "11") (pinfunction "5A_11") (pintype "unspecified"))
      (node (ref "K1") (pin "13") (pinfunction "6A_13") (pintype "unspecified"))
      (node (ref "K1") (pin "7") (pinfunction "GND_7") (pintype "unspecified"))
      (node (ref "K2") (pin "13") (pinfunction "OE#_13") (pintype "unspecified"))
      (node (ref "K2") (pin "8") (pinfunction "GND_8") (pintype "unspecified"))
      (node (ref "K3") (pin "13") (pinfunction "OE#_13") (pintype "unspecified"))
      (node (ref "K3") (pin "8") (pinfunction "GND_8") (pintype "unspecified"))
      (node (ref "KEYBOARD") (pin "3") (pinfunction "GND_3") (pintype "passive"))
      (node (ref "PXS") (pin "15") (pinfunction "CLK/INH_15") (pintype "unspecified"))
      (node (ref "PXS") (pin "8") (pinfunction "GND_8") (pintype "unspecified"))
      (node (ref "R10") (pin "1") (pinfunction "1_1") (pintype "unspecified"))
      (node (ref "R11") (pin "1") (pinfunction "1_1") (pintype "unspecified"))
      (node (ref "R12") (pin "1") (pinfunction "1_1") (pintype "unspecified"))
      (node (ref "R13") (pin "1") (pinfunction "1_1") (pintype "unspecified"))
      (node (ref "R14") (pin "1") (pinfunction "1_1") (pintype "unspecified"))
      (node (ref "R15") (pin "1") (pinfunction "1_1") (pintype "unspecified"))
      (node (ref "R16") (pin "1") (pinfunction "1_1") (pintype "unspecified"))
      (node (ref "R17") (pin "1") (pinfunction "1_1") (pintype "unspecified"))
      (node (ref "R2") (pin "1") (pinfunction "1_1") (pintype "unspecified"))
      (node (ref "R3") (pin "1") (pinfunction "1_1") (pintype "unspecified"))
      (node (ref "R4") (pin "2") (pinfunction "2_2") (pintype "unspecified"))
      (node (ref "R5") (pin "2") (pinfunction "2_2") (pintype "unspecified"))
      (node (ref "R6") (pin "2") (pinfunction "2_2") (pintype "unspecified"))
      (node (ref "RAM") (pin "14") (pinfunction "GND_14") (pintype "unspecified"))
      (node (ref "RAM") (pin "22") (pinfunction "!OE_22") (pintype "input"))
      (node (ref "RC") (pin "8") (pinfunction "GND_8") (pintype "bidirectional"))
      (node (ref "ROM") (pin "1") (pinfunction "A14_1") (pintype "input"))
      (node (ref "ROM") (pin "14") (pinfunction "GND_14") (pintype "passive"))
      (node (ref "ROM") (pin "22") (pinfunction "/OE_22") (pintype "input"))
      (node (ref "SW1") (pin "1") (pinfunction "1_1") (pintype "unspecified"))
      (node (ref "T8") (pin "7") (pinfunction "GND_7") (pintype "unspecified"))
      (node (ref "VA") (pin "7") (pinfunction "GND_7") (pintype "unspecified"))
      (node (ref "VC") (pin "8") (pinfunction "GND_8") (pintype "unspecified"))
      (node (ref "VCI") (pin "7") (pinfunction "GND_7") (pintype "unspecified"))
      (node (ref "VCT") (pin "7") (pinfunction "GND_7") (pintype "unspecified"))
      (node (ref "VIA") (pin "1") (pinfunction "GND_1") (pintype "unspecified"))
      (node (ref "VIA2") (pin "1") (pinfunction "GND_1") (pintype "unspecified"))
      (node (ref "VRAM") (pin "1") (pinfunction "!CEL_1") (pintype "unspecified"))
      (node (ref "VRAM") (pin "24") (pinfunction "Gnd_24") (pintype "unspecified"))
      (node (ref "VRAM") (pin "3") (pinfunction "!BUSYL_3") (pintype "unspecified"))
      (node (ref "VRAM") (pin "43") (pinfunction "!OER_43") (pintype "unspecified"))
      (node (ref "VRAM") (pin "5") (pinfunction "!OEL_5") (pintype "unspecified"))
      (node (ref "X2") (pin "7") (pinfunction "GND_7") (pintype "unspecified"))
    )
    (net (code "67") (name "Hsync") (class "Default")
      (node (ref "DSUB2") (pin "13") (pinfunction "HSYNC_13") (pintype "unspecified"))
      (node (ref "HCT") (pin "12") (pinfunction "4A_12") (pintype "unspecified"))
      (node (ref "HCT") (pin "8") (pinfunction "3Y_8") (pintype "unspecified"))
      (node (ref "HS") (pin "1") (pinfunction "Hs_1") (pintype "input"))
      (node (ref "VCT") (pin "1") (pinfunction "1A_1") (pintype "unspecified"))
      (node (ref "VCT") (pin "2") (pinfunction "1B_2") (pintype "unspecified"))
    )
    (net (code "68") (name "Hsynci") (class "Default")
      (node (ref "CC") (pin "11") (pinfunction "CLR_11") (pintype "bidirectional"))
      (node (ref "VCT") (pin "3") (pinfunction "1Y_3") (pintype "unspecified"))
    )
    (net (code "69") (name "Net-(528-3B)") (class "Default")
      (node (ref "528") (pin "10") (pinfunction "3B_10") (pintype "unspecified"))
      (node (ref "528") (pin "11") (pinfunction "4Y_11") (pintype "unspecified"))
    )
    (net (code "70") (name "Net-(ACIA--DTR)") (class "Default")
      (node (ref "ACIA") (pin "11") (pinfunction "-DTR_11") (pintype "unspecified"))
      (node (ref "LED2") (pin "1") (pinfunction "1_1") (pintype "unspecified"))
    )
    (net (code "71") (name "Net-(ACIA--RES)") (class "Default")
      (node (ref "ACIA") (pin "4") (pinfunction "-RES_4") (pintype "unspecified"))
      (node (ref "CPU") (pin "40") (pinfunction "RESB_40") (pintype "input"))
      (node (ref "SW1") (pin "4") (pinfunction "4_4") (pintype "unspecified"))
      (node (ref "VIA") (pin "34") (pinfunction "/RES_34") (pintype "unspecified"))
      (node (ref "VIA2") (pin "34") (pinfunction "/RES_34") (pintype "unspecified"))
    )
    (net (code "72") (name "Net-(ACIA-PHI2)") (class "Default")
      (node (ref "ACIA") (pin "27") (pinfunction "PHI2_27") (pintype "unspecified"))
      (node (ref "CPU") (pin "37") (pinfunction "PH0-IN_37") (pintype "input"))
      (node (ref "VIA") (pin "25") (pinfunction "PHI2_25") (pintype "unspecified"))
      (node (ref "VIA2") (pin "25") (pinfunction "PHI2_25") (pintype "unspecified"))
    )
    (net (code "73") (name "Net-(ACIA-RxD)") (class "Default")
      (node (ref "ACIA") (pin "12") (pinfunction "RxD_12") (pintype "unspecified"))
      (node (ref "LED4") (pin "1") (pinfunction "1_1") (pintype "unspecified"))
      (node (ref "R3") (pin "2") (pinfunction "2_2") (pintype "unspecified"))
      (node (ref "RX") (pin "1") (pinfunction "2_1") (pintype "input"))
    )
    (net (code "74") (name "Net-(ACIA-R{slash}W)") (class "Default")
      (node (ref "ACIA") (pin "28") (pinfunction "R/W_28") (pintype "unspecified"))
      (node (ref "CPU") (pin "34") (pinfunction "RWB_34") (pintype "output"))
      (node (ref "RAM") (pin "27") (pinfunction "!WE_27") (pintype "input"))
      (node (ref "VIA") (pin "22") (pinfunction "R/W_22") (pintype "unspecified"))
      (node (ref "VIA2") (pin "22") (pinfunction "R/W_22") (pintype "unspecified"))
      (node (ref "VRAM") (pin "46") (pinfunction "R/!WR_46") (pintype "unspecified"))
    )
    (net (code "75") (name "Net-(ACIA-TxD)") (class "Default")
      (node (ref "ACIA") (pin "10") (pinfunction "TxD_10") (pintype "unspecified"))
      (node (ref "LED3") (pin "1") (pinfunction "1_1") (pintype "unspecified"))
      (node (ref "R2") (pin "2") (pinfunction "2_2") (pintype "unspecified"))
      (node (ref "TX") (pin "1") (pinfunction "1_1") (pintype "input"))
    )
    (net (code "76") (name "Net-(ACIA-XTLI)") (class "Default")
      (node (ref "ACIA") (pin "6") (pinfunction "XTLI_6") (pintype "unspecified"))
      (node (ref "C1") (pin "2") (pinfunction "2_2") (pintype "unspecified"))
      (node (ref "X1") (pin "2") (pinfunction "OSC2_2") (pintype "input"))
    )
    (net (code "77") (name "Net-(ACIA-XTLO)") (class "Default")
      (node (ref "ACIA") (pin "7") (pinfunction "XTLO_7") (pintype "unspecified"))
      (node (ref "X1") (pin "1") (pinfunction "OSC1_1") (pintype "input"))
    )
    (net (code "78") (name "Net-(AD1-1Y)") (class "Default")
      (node (ref "AD1") (pin "3") (pinfunction "1Y_3") (pintype "unspecified"))
      (node (ref "AD1") (pin "4") (pinfunction "2A_4") (pintype "unspecified"))
    )
    (net (code "79") (name "Net-(AD1-2Y)") (class "Default")
      (node (ref "AD1") (pin "6") (pinfunction "2Y_6") (pintype "unspecified"))
      (node (ref "RAM") (pin "20") (pinfunction "!CE_20") (pintype "input"))
    )
    (net (code "80") (name "Net-(AD2-1Y)") (class "Default")
      (node (ref "AD2") (pin "3") (pinfunction "1Y_3") (pintype "unspecified"))
      (node (ref "AD2") (pin "4") (pinfunction "2A_4") (pintype "unspecified"))
      (node (ref "AD2") (pin "5") (pinfunction "2B_5") (pintype "unspecified"))
    )
    (net (code "81") (name "Net-(AD2-2Y)") (class "Default")
      (node (ref "AD2") (pin "13") (pinfunction "4B_13") (pintype "unspecified"))
      (node (ref "AD2") (pin "6") (pinfunction "2Y_6") (pintype "unspecified"))
    )
    (net (code "82") (name "Net-(CC-QA)") (class "Default")
      (node (ref "CC") (pin "9") (pinfunction "QA_9") (pintype "bidirectional"))
      (node (ref "VRAM") (pin "6") (pinfunction "A0L_6") (pintype "unspecified"))
    )
    (net (code "83") (name "Net-(CC-QB)") (class "Default")
      (node (ref "CC") (pin "7") (pinfunction "QB_7") (pintype "bidirectional"))
      (node (ref "VRAM") (pin "7") (pinfunction "A1L_7") (pintype "unspecified"))
    )
    (net (code "84") (name "Net-(CC-QC)") (class "Default")
      (node (ref "CC") (pin "6") (pinfunction "QC_6") (pintype "bidirectional"))
      (node (ref "VRAM") (pin "8") (pinfunction "A2L_8") (pintype "unspecified"))
    )
    (net (code "85") (name "Net-(CC-QD)") (class "Default")
      (node (ref "CC") (pin "5") (pinfunction "QD_5") (pintype "bidirectional"))
      (node (ref "VRAM") (pin "9") (pinfunction "A3L_9") (pintype "unspecified"))
    )
    (net (code "86") (name "Net-(CC-QE)") (class "Default")
      (node (ref "CC") (pin "3") (pinfunction "QE_3") (pintype "bidirectional"))
      (node (ref "VRAM") (pin "10") (pinfunction "A4L_10") (pintype "unspecified"))
    )
    (net (code "87") (name "Net-(CC-QF)") (class "Default")
      (node (ref "CC") (pin "2") (pinfunction "QF_2") (pintype "bidirectional"))
      (node (ref "VRAM") (pin "11") (pinfunction "A5L_11") (pintype "unspecified"))
    )
    (net (code "88") (name "Net-(CLK-2)") (class "Default")
      (node (ref "CLK") (pin "1") (pinfunction "2_1") (pintype "input"))
      (node (ref "K1") (pin "1") (pinfunction "1A_1") (pintype "unspecified"))
      (node (ref "K1") (pin "9") (pinfunction "4A_9") (pintype "unspecified"))
      (node (ref "KEYBOARD") (pin "5") (pinfunction "CLK_5") (pintype "unspecified"))
    )
    (net (code "89") (name "Net-(CPU-IRQB)") (class "Default")
      (node (ref "CPU") (pin "4") (pinfunction "IRQB_4") (pintype "input"))
      (node (ref "R9") (pin "1") (pinfunction "1_1") (pintype "unspecified"))
      (node (ref "VIA") (pin "21") (pinfunction "/IRQ_21") (pintype "unspecified"))
      (node (ref "VIA2") (pin "21") (pinfunction "/IRQ_21") (pintype "unspecified"))
    )
    (net (code "90") (name "Net-(CROM-A3)") (class "Default")
      (node (ref "CROM") (pin "7") (pinfunction "A3_7") (pintype "unspecified"))
      (node (ref "VRAM") (pin "16") (pinfunction "D0L_16") (pintype "unspecified"))
    )
    (net (code "91") (name "Net-(CROM-A4)") (class "Default")
      (node (ref "CROM") (pin "6") (pinfunction "A4_6") (pintype "unspecified"))
      (node (ref "VRAM") (pin "17") (pinfunction "D1L_17") (pintype "unspecified"))
    )
    (net (code "92") (name "Net-(CROM-A5)") (class "Default")
      (node (ref "CROM") (pin "5") (pinfunction "A5_5") (pintype "unspecified"))
      (node (ref "VRAM") (pin "18") (pinfunction "D2L_18") (pintype "unspecified"))
    )
    (net (code "93") (name "Net-(CROM-A6)") (class "Default")
      (node (ref "CROM") (pin "4") (pinfunction "A6_4") (pintype "unspecified"))
      (node (ref "VRAM") (pin "19") (pinfunction "D3L_19") (pintype "unspecified"))
    )
    (net (code "94") (name "Net-(CROM-A7)") (class "Default")
      (node (ref "CROM") (pin "3") (pinfunction "A7_3") (pintype "unspecified"))
      (node (ref "VRAM") (pin "20") (pinfunction "D4L_20") (pintype "unspecified"))
    )
    (net (code "95") (name "Net-(CROM-A8)") (class "Default")
      (node (ref "CROM") (pin "25") (pinfunction "A8_25") (pintype "unspecified"))
      (node (ref "VRAM") (pin "21") (pinfunction "D5L_21") (pintype "unspecified"))
    )
    (net (code "96") (name "Net-(CROM-A9)") (class "Default")
      (node (ref "CROM") (pin "24") (pinfunction "A9_24") (pintype "unspecified"))
      (node (ref "VRAM") (pin "22") (pinfunction "D6L_22") (pintype "unspecified"))
    )
    (net (code "97") (name "Net-(CROM-A10)") (class "Default")
      (node (ref "CROM") (pin "21") (pinfunction "A10_21") (pintype "unspecified"))
      (node (ref "VRAM") (pin "23") (pinfunction "D7L_23") (pintype "unspecified"))
    )
    (net (code "98") (name "Net-(CROM-A11)") (class "Default")
      (node (ref "CROM") (pin "23") (pinfunction "A11_23") (pintype "unspecified"))
      (node (ref "H9") (pin "1") (pinfunction "1_1") (pintype "unspecified"))
    )
    (net (code "99") (name "Net-(CROM-A12)") (class "Default")
      (node (ref "CROM") (pin "2") (pinfunction "A12_2") (pintype "unspecified"))
      (node (ref "H9") (pin "3") (pinfunction "3_3") (pintype "unspecified"))
    )
    (net (code "100") (name "Net-(CROM-D0)") (class "Default")
      (node (ref "CROM") (pin "11") (pinfunction "D0_11") (pintype "unspecified"))
      (node (ref "PXS") (pin "11") (pinfunction "A_11") (pintype "unspecified"))
    )
    (net (code "101") (name "Net-(CROM-D1)") (class "Default")
      (node (ref "CROM") (pin "12") (pinfunction "D1_12") (pintype "unspecified"))
      (node (ref "PXS") (pin "12") (pinfunction "B_12") (pintype "unspecified"))
    )
    (net (code "102") (name "Net-(CROM-D2)") (class "Default")
      (node (ref "CROM") (pin "13") (pinfunction "D2_13") (pintype "unspecified"))
      (node (ref "PXS") (pin "13") (pinfunction "C_13") (pintype "unspecified"))
    )
    (net (code "103") (name "Net-(CROM-D3)") (class "Default")
      (node (ref "CROM") (pin "15") (pinfunction "D3_15") (pintype "unspecified"))
      (node (ref "PXS") (pin "14") (pinfunction "D_14") (pintype "unspecified"))
    )
    (net (code "104") (name "Net-(CROM-D4)") (class "Default")
      (node (ref "CROM") (pin "16") (pinfunction "D4_16") (pintype "unspecified"))
      (node (ref "PXS") (pin "3") (pinfunction "E_3") (pintype "unspecified"))
    )
    (net (code "105") (name "Net-(CROM-D5)") (class "Default")
      (node (ref "CROM") (pin "17") (pinfunction "D5_17") (pintype "unspecified"))
      (node (ref "PXS") (pin "4") (pinfunction "F_4") (pintype "unspecified"))
    )
    (net (code "106") (name "Net-(CROM-D6)") (class "Default")
      (node (ref "CROM") (pin "18") (pinfunction "D6_18") (pintype "unspecified"))
      (node (ref "PXS") (pin "5") (pinfunction "G_5") (pintype "unspecified"))
    )
    (net (code "107") (name "Net-(CROM-D7)") (class "Default")
      (node (ref "CROM") (pin "19") (pinfunction "D7_19") (pintype "unspecified"))
      (node (ref "PXS") (pin "6") (pinfunction "H_6") (pintype "unspecified"))
    )
    (net (code "108") (name "Net-(CROM-OE)") (class "Default")
      (node (ref "CROM") (pin "22") (pinfunction "OE_22") (pintype "unspecified"))
      (node (ref "RC") (pin "2") (pinfunction "QF_2") (pintype "bidirectional"))
    )
    (net (code "109") (name "Net-(HCT-1Y)") (class "Default")
      (node (ref "HCT") (pin "3") (pinfunction "1Y_3") (pintype "unspecified"))
      (node (ref "HCT") (pin "4") (pinfunction "2A_4") (pintype "unspecified"))
    )
    (net (code "110") (name "Net-(HCT-3A)") (class "Default")
      (node (ref "HCT") (pin "11") (pinfunction "4Y_11") (pintype "unspecified"))
      (node (ref "HCT") (pin "9") (pinfunction "3A_9") (pintype "unspecified"))
    )
    (net (code "111") (name "Net-(K1-1Y)") (class "Default")
      (node (ref "D1") (pin "2") (pinfunction "2_2") (pintype "unspecified"))
      (node (ref "K1") (pin "2") (pinfunction "1Y_2") (pintype "unspecified"))
      (node (ref "R7") (pin "1") (pinfunction "1_1") (pintype "unspecified"))
    )
    (net (code "112") (name "Net-(K1-2A)") (class "Default")
      (node (ref "C2") (pin "1") (pinfunction "1_1") (pintype "unspecified"))
      (node (ref "D1") (pin "1") (pinfunction "1_1") (pintype "unspecified"))
      (node (ref "K1") (pin "3") (pinfunction "2A_3") (pintype "unspecified"))
      (node (ref "R7") (pin "2") (pinfunction "2_2") (pintype "unspecified"))
    )
    (net (code "113") (name "Net-(K1-2Y)") (class "Default")
      (node (ref "K1") (pin "4") (pinfunction "2Y_4") (pintype "unspecified"))
      (node (ref "K1") (pin "5") (pinfunction "3A_5") (pintype "unspecified"))
      (node (ref "K2") (pin "12") (pinfunction "RCLK_12") (pintype "unspecified"))
      (node (ref "K3") (pin "12") (pinfunction "RCLK_12") (pintype "unspecified"))
      (node (ref "VIA") (pin "40") (pinfunction "CA1_40") (pintype "unspecified"))
    )
    (net (code "114") (name "Net-(K1-4Y)") (class "Default")
      (node (ref "K1") (pin "8") (pinfunction "4Y_8") (pintype "unspecified"))
      (node (ref "K2") (pin "11") (pinfunction "SRCLK_11") (pintype "unspecified"))
      (node (ref "K3") (pin "11") (pinfunction "SRCLK_11") (pintype "unspecified"))
    )
    (net (code "115") (name "Net-(K2-QC)") (class "Default")
      (node (ref "K2") (pin "2") (pinfunction "QC_2") (pintype "unspecified"))
      (node (ref "LED13") (pin "1") (pinfunction "1_1") (pintype "unspecified"))
    )
    (net (code "116") (name "Net-(K2-QD)") (class "Default")
      (node (ref "K2") (pin "3") (pinfunction "QD_3") (pintype "unspecified"))
      (node (ref "LED12") (pin "1") (pinfunction "1_1") (pintype "unspecified"))
    )
    (net (code "117") (name "Net-(K2-QE)") (class "Default")
      (node (ref "K2") (pin "4") (pinfunction "QE_4") (pintype "unspecified"))
      (node (ref "LED11") (pin "1") (pinfunction "1_1") (pintype "unspecified"))
    )
    (net (code "118") (name "Net-(K2-QF)") (class "Default")
      (node (ref "K2") (pin "5") (pinfunction "QF_5") (pintype "unspecified"))
      (node (ref "LED10") (pin "1") (pinfunction "1_1") (pintype "unspecified"))
    )
    (net (code "119") (name "Net-(K2-QG)") (class "Default")
      (node (ref "K2") (pin "6") (pinfunction "QG_6") (pintype "unspecified"))
      (node (ref "LED9") (pin "1") (pinfunction "1_1") (pintype "unspecified"))
    )
    (net (code "120") (name "Net-(K2-QH&apos;)") (class "Default")
      (node (ref "K2") (pin "9") (pinfunction "QH&apos;_9") (pintype "unspecified"))
      (node (ref "K3") (pin "14") (pinfunction "SER_14") (pintype "unspecified"))
    )
    (net (code "121") (name "Net-(K2-QH)") (class "Default")
      (node (ref "K2") (pin "7") (pinfunction "QH_7") (pintype "unspecified"))
      (node (ref "LED8") (pin "1") (pinfunction "1_1") (pintype "unspecified"))
    )
    (net (code "122") (name "Net-(K2-SER)") (class "Default")
      (node (ref "DATA") (pin "1") (pinfunction "1_1") (pintype "input"))
      (node (ref "K2") (pin "14") (pinfunction "SER_14") (pintype "unspecified"))
      (node (ref "KEYBOARD") (pin "1") (pinfunction "DATA_1") (pintype "input"))
    )
    (net (code "123") (name "Net-(K3-QA)") (class "Default")
      (node (ref "K3") (pin "15") (pinfunction "QA_15") (pintype "unspecified"))
      (node (ref "LED7") (pin "1") (pinfunction "1_1") (pintype "unspecified"))
    )
    (net (code "124") (name "Net-(K3-QB)") (class "Default")
      (node (ref "K3") (pin "1") (pinfunction "QB_1") (pintype "unspecified"))
      (node (ref "LED6") (pin "1") (pinfunction "1_1") (pintype "unspecified"))
    )
    (net (code "125") (name "Net-(LED2-Pad2)") (class "Default")
      (node (ref "LED2") (pin "2") (pinfunction "2_2") (pintype "unspecified"))
      (node (ref "R6") (pin "1") (pinfunction "1_1") (pintype "unspecified"))
    )
    (net (code "126") (name "Net-(LED3-Pad2)") (class "Default")
      (node (ref "LED3") (pin "2") (pinfunction "2_2") (pintype "unspecified"))
      (node (ref "R4") (pin "1") (pinfunction "1_1") (pintype "unspecified"))
    )
    (net (code "127") (name "Net-(LED4-Pad2)") (class "Default")
      (node (ref "LED4") (pin "2") (pinfunction "2_2") (pintype "unspecified"))
      (node (ref "R5") (pin "1") (pinfunction "1_1") (pintype "unspecified"))
    )
    (net (code "128") (name "Net-(R1-Pad2)") (class "Default")
      (node (ref "R1") (pin "2") (pinfunction "2_2") (pintype "unspecified"))
      (node (ref "SW1") (pin "3") (pinfunction "3_3") (pintype "unspecified"))
    )
    (net (code "129") (name "Net-(RC-QA)") (class "Default")
      (node (ref "RC") (pin "9") (pinfunction "QA_9") (pintype "bidirectional"))
      (node (ref "VRAM") (pin "12") (pinfunction "A6L_12") (pintype "unspecified"))
    )
    (net (code "130") (name "Net-(RC-QB)") (class "Default")
      (node (ref "RC") (pin "7") (pinfunction "QB_7") (pintype "bidirectional"))
      (node (ref "VRAM") (pin "13") (pinfunction "A7L_13") (pintype "unspecified"))
    )
    (net (code "131") (name "Net-(RC-QC)") (class "Default")
      (node (ref "RC") (pin "6") (pinfunction "QC_6") (pintype "bidirectional"))
      (node (ref "VRAM") (pin "14") (pinfunction "A8L_14") (pintype "unspecified"))
    )
    (net (code "132") (name "Net-(RC-QD)") (class "Default")
      (node (ref "RC") (pin "5") (pinfunction "QD_5") (pintype "bidirectional"))
      (node (ref "VRAM") (pin "15") (pinfunction "A9L_15") (pintype "unspecified"))
    )
    (net (code "133") (name "Net-(RC-QE)") (class "Default")
      (node (ref "RC") (pin "3") (pinfunction "QE_3") (pintype "bidirectional"))
      (node (ref "VRAM") (pin "4") (pinfunction "A10L_4") (pintype "unspecified"))
    )
    (net (code "134") (name "Net-(RGB-rgb)") (class "Default")
      (node (ref "R8") (pin "1") (pinfunction "1_1") (pintype "unspecified"))
      (node (ref "RGB") (pin "1") (pinfunction "rgb_1") (pintype "input"))
    )
    (net (code "135") (name "Net-(VA-1Y)") (class "Default")
      (node (ref "VA") (pin "3") (pinfunction "1Y_3") (pintype "unspecified"))
      (node (ref "VA") (pin "4") (pinfunction "2A_4") (pintype "unspecified"))
      (node (ref "VA") (pin "5") (pinfunction "2B_5") (pintype "unspecified"))
    )
    (net (code "136") (name "Net-(VA-3A)") (class "Default")
      (node (ref "VA") (pin "10") (pinfunction "3B_10") (pintype "unspecified"))
      (node (ref "VA") (pin "11") (pinfunction "4Y_11") (pintype "unspecified"))
      (node (ref "VA") (pin "9") (pinfunction "3A_9") (pintype "unspecified"))
    )
    (net (code "137") (name "Net-(VCT-3Y)") (class "Default")
      (node (ref "VCT") (pin "12") (pinfunction "4A_12") (pintype "unspecified"))
      (node (ref "VCT") (pin "8") (pinfunction "3Y_8") (pintype "unspecified"))
    )
    (net (code "138") (name "Net-(VIA-PA0)") (class "Default")
      (node (ref "LED6") (pin "2") (pinfunction "2_2") (pintype "unspecified"))
      (node (ref "R10") (pin "2") (pinfunction "2_2") (pintype "unspecified"))
      (node (ref "VIA") (pin "2") (pinfunction "PA0_2") (pintype "unspecified"))
    )
    (net (code "139") (name "Net-(VIA-PA1)") (class "Default")
      (node (ref "LED7") (pin "2") (pinfunction "2_2") (pintype "unspecified"))
      (node (ref "R11") (pin "2") (pinfunction "2_2") (pintype "unspecified"))
      (node (ref "VIA") (pin "3") (pinfunction "PA1_3") (pintype "unspecified"))
    )
    (net (code "140") (name "Net-(VIA-PA2)") (class "Default")
      (node (ref "LED8") (pin "2") (pinfunction "2_2") (pintype "unspecified"))
      (node (ref "R12") (pin "2") (pinfunction "2_2") (pintype "unspecified"))
      (node (ref "VIA") (pin "4") (pinfunction "PA2_4") (pintype "unspecified"))
    )
    (net (code "141") (name "Net-(VIA-PA3)") (class "Default")
      (node (ref "LED9") (pin "2") (pinfunction "2_2") (pintype "unspecified"))
      (node (ref "R13") (pin "2") (pinfunction "2_2") (pintype "unspecified"))
      (node (ref "VIA") (pin "5") (pinfunction "PA3_5") (pintype "unspecified"))
    )
    (net (code "142") (name "Net-(VIA-PA4)") (class "Default")
      (node (ref "LED10") (pin "2") (pinfunction "2_2") (pintype "unspecified"))
      (node (ref "R14") (pin "2") (pinfunction "2_2") (pintype "unspecified"))
      (node (ref "VIA") (pin "6") (pinfunction "PA4_6") (pintype "unspecified"))
    )
    (net (code "143") (name "Net-(VIA-PA5)") (class "Default")
      (node (ref "LED11") (pin "2") (pinfunction "2_2") (pintype "unspecified"))
      (node (ref "R15") (pin "2") (pinfunction "2_2") (pintype "unspecified"))
      (node (ref "VIA") (pin "7") (pinfunction "PA5_7") (pintype "unspecified"))
    )
    (net (code "144") (name "Net-(VIA-PA6)") (class "Default")
      (node (ref "LED12") (pin "2") (pinfunction "2_2") (pintype "unspecified"))
      (node (ref "R16") (pin "2") (pinfunction "2_2") (pintype "unspecified"))
      (node (ref "VIA") (pin "8") (pinfunction "PA6_8") (pintype "unspecified"))
    )
    (net (code "145") (name "Net-(VIA-PA7)") (class "Default")
      (node (ref "LED13") (pin "2") (pinfunction "2_2") (pintype "unspecified"))
      (node (ref "R17") (pin "2") (pinfunction "2_2") (pintype "unspecified"))
      (node (ref "VIA") (pin "9") (pinfunction "PA7_9") (pintype "unspecified"))
    )
    (net (code "146") (name "Net-(VIA-PB0)") (class "Default")
      (node (ref "PORTB") (pin "1") (pinfunction "1_1") (pintype "unspecified"))
      (node (ref "VIA") (pin "10") (pinfunction "PB0_10") (pintype "unspecified"))
    )
    (net (code "147") (name "Net-(VIA-PB1)") (class "Default")
      (node (ref "PORTB") (pin "2") (pinfunction "2_2") (pintype "unspecified"))
      (node (ref "VIA") (pin "11") (pinfunction "PB1_11") (pintype "unspecified"))
    )
    (net (code "148") (name "Net-(VIA-PB2)") (class "Default")
      (node (ref "PORTB") (pin "3") (pinfunction "3_3") (pintype "unspecified"))
      (node (ref "VIA") (pin "12") (pinfunction "PB2_12") (pintype "unspecified"))
    )
    (net (code "149") (name "Net-(VIA-PB3)") (class "Default")
      (node (ref "PORTB") (pin "4") (pinfunction "4_4") (pintype "unspecified"))
      (node (ref "VIA") (pin "13") (pinfunction "PB3_13") (pintype "unspecified"))
    )
    (net (code "150") (name "Net-(VIA-PB4)") (class "Default")
      (node (ref "PORTB") (pin "5") (pinfunction "5_5") (pintype "unspecified"))
      (node (ref "VIA") (pin "14") (pinfunction "PB4_14") (pintype "unspecified"))
    )
    (net (code "151") (name "Net-(VIA-PB5)") (class "Default")
      (node (ref "PORTB") (pin "6") (pinfunction "6_6") (pintype "unspecified"))
      (node (ref "VIA") (pin "15") (pinfunction "PB5_15") (pintype "unspecified"))
    )
    (net (code "152") (name "Net-(VIA-PB6)") (class "Default")
      (node (ref "PORTB") (pin "7") (pinfunction "7_7") (pintype "unspecified"))
      (node (ref "VIA") (pin "16") (pinfunction "PB6_16") (pintype "unspecified"))
    )
    (net (code "153") (name "Net-(VIA-PB7)") (class "Default")
      (node (ref "PORTB") (pin "8") (pinfunction "8_8") (pintype "unspecified"))
      (node (ref "VIA") (pin "17") (pinfunction "PB7_17") (pintype "unspecified"))
    )
    (net (code "154") (name "Net-(VIA2-PA0)") (class "Default")
      (node (ref "P2") (pin "1") (pinfunction "1_1") (pintype "unspecified"))
      (node (ref "VIA2") (pin "2") (pinfunction "PA0_2") (pintype "unspecified"))
    )
    (net (code "155") (name "Net-(VIA2-PA1)") (class "Default")
      (node (ref "P2") (pin "2") (pinfunction "2_2") (pintype "unspecified"))
      (node (ref "VIA2") (pin "3") (pinfunction "PA1_3") (pintype "unspecified"))
    )
    (net (code "156") (name "Net-(VIA2-PA2)") (class "Default")
      (node (ref "P2") (pin "3") (pinfunction "3_3") (pintype "unspecified"))
      (node (ref "VIA2") (pin "4") (pinfunction "PA2_4") (pintype "unspecified"))
    )
    (net (code "157") (name "Net-(VIA2-PA3)") (class "Default")
      (node (ref "P2") (pin "4") (pinfunction "4_4") (pintype "unspecified"))
      (node (ref "VIA2") (pin "5") (pinfunction "PA3_5") (pintype "unspecified"))
    )
    (net (code "158") (name "Net-(VIA2-PA4)") (class "Default")
      (node (ref "P2") (pin "5") (pinfunction "5_5") (pintype "unspecified"))
      (node (ref "VIA2") (pin "6") (pinfunction "PA4_6") (pintype "unspecified"))
    )
    (net (code "159") (name "Net-(VIA2-PA5)") (class "Default")
      (node (ref "P2") (pin "6") (pinfunction "6_6") (pintype "unspecified"))
      (node (ref "VIA2") (pin "7") (pinfunction "PA5_7") (pintype "unspecified"))
    )
    (net (code "160") (name "Net-(VIA2-PA6)") (class "Default")
      (node (ref "P2") (pin "7") (pinfunction "7_7") (pintype "unspecified"))
      (node (ref "VIA2") (pin "8") (pinfunction "PA6_8") (pintype "unspecified"))
    )
    (net (code "161") (name "Net-(VIA2-PA7)") (class "Default")
      (node (ref "P2") (pin "8") (pinfunction "8_8") (pintype "unspecified"))
      (node (ref "VIA2") (pin "9") (pinfunction "PA7_9") (pintype "unspecified"))
    )
    (net (code "162") (name "Net-(VIA2-PB0)") (class "Default")
      (node (ref "P3") (pin "1") (pinfunction "1_1") (pintype "unspecified"))
      (node (ref "VIA2") (pin "10") (pinfunction "PB0_10") (pintype "unspecified"))
    )
    (net (code "163") (name "Net-(VIA2-PB1)") (class "Default")
      (node (ref "P3") (pin "2") (pinfunction "2_2") (pintype "unspecified"))
      (node (ref "VIA2") (pin "11") (pinfunction "PB1_11") (pintype "unspecified"))
    )
    (net (code "164") (name "Net-(VIA2-PB2)") (class "Default")
      (node (ref "P3") (pin "3") (pinfunction "3_3") (pintype "unspecified"))
      (node (ref "VIA2") (pin "12") (pinfunction "PB2_12") (pintype "unspecified"))
    )
    (net (code "165") (name "Net-(VIA2-PB3)") (class "Default")
      (node (ref "P3") (pin "4") (pinfunction "4_4") (pintype "unspecified"))
      (node (ref "VIA2") (pin "13") (pinfunction "PB3_13") (pintype "unspecified"))
    )
    (net (code "166") (name "Net-(VIA2-PB4)") (class "Default")
      (node (ref "P3") (pin "5") (pinfunction "5_5") (pintype "unspecified"))
      (node (ref "VIA2") (pin "14") (pinfunction "PB4_14") (pintype "unspecified"))
    )
    (net (code "167") (name "Net-(VIA2-PB5)") (class "Default")
      (node (ref "P3") (pin "6") (pinfunction "6_6") (pintype "unspecified"))
      (node (ref "VIA2") (pin "15") (pinfunction "PB5_15") (pintype "unspecified"))
    )
    (net (code "168") (name "Net-(VIA2-PB6)") (class "Default")
      (node (ref "P3") (pin "7") (pinfunction "7_7") (pintype "unspecified"))
      (node (ref "VIA2") (pin "16") (pinfunction "PB6_16") (pintype "unspecified"))
    )
    (net (code "169") (name "Net-(VIA2-PB7)") (class "Default")
      (node (ref "P3") (pin "8") (pinfunction "8_8") (pintype "unspecified"))
      (node (ref "VIA2") (pin "17") (pinfunction "PB7_17") (pintype "unspecified"))
    )
    (net (code "170") (name "SCLK") (class "Default")
      (node (ref "420") (pin "2") (pinfunction "B_2") (pintype "unspecified"))
      (node (ref "484") (pin "2") (pinfunction "B_2") (pintype "unspecified"))
      (node (ref "AD1") (pin "5") (pinfunction "2B_5") (pintype "unspecified"))
      (node (ref "AD3") (pin "15") (pinfunction "A0_15") (pintype "unspecified"))
      (node (ref "HC") (pin "6") (pinfunction "QC_6") (pintype "unspecified"))
      (node (ref "HCI") (pin "3") (pinfunction "2A_3") (pintype "unspecified"))
      (node (ref "T8") (pin "1") (pinfunction "A_1") (pintype "unspecified"))
      (node (ref "T8") (pin "2") (pinfunction "B_2") (pintype "unspecified"))
      (node (ref "T8") (pin "3") (pinfunction "C_3") (pintype "unspecified"))
      (node (ref "T8") (pin "4") (pinfunction "D_4") (pintype "unspecified"))
      (node (ref "T8") (pin "5") (pinfunction "E_5") (pintype "unspecified"))
      (node (ref "T8") (pin "6") (pinfunction "F_6") (pintype "unspecified"))
      (node (ref "VCT") (pin "4") (pinfunction "2A_4") (pintype "unspecified"))
    )
    (net (code "171") (name "VAi") (class "Default")
      (node (ref "VA") (pin "13") (pinfunction "4B_13") (pintype "unspecified"))
      (node (ref "VA") (pin "6") (pinfunction "2Y_6") (pintype "unspecified"))
      (node (ref "VCT") (pin "5") (pinfunction "2B_5") (pintype "unspecified"))
    )
    (net (code "172") (name "VCC") (class "Default")
      (node (ref "400") (pin "14") (pinfunction "VCC_14") (pintype "unspecified"))
      (node (ref "420") (pin "14") (pinfunction "VCC_14") (pintype "unspecified"))
      (node (ref "484") (pin "14") (pinfunction "VCC_14") (pintype "unspecified"))
      (node (ref "528") (pin "14") (pinfunction "VCC_14") (pintype "unspecified"))
      (node (ref "600") (pin "14") (pinfunction "VCC_14") (pintype "unspecified"))
      (node (ref "601") (pin "14") (pinfunction "VCC_14") (pintype "unspecified"))
      (node (ref "605") (pin "14") (pinfunction "VCC_14") (pintype "unspecified"))
      (node (ref "628") (pin "14") (pinfunction "VCC_14") (pintype "unspecified"))
      (node (ref "ACIA") (pin "15") (pinfunction "VCC_15") (pintype "unspecified"))
      (node (ref "AD1") (pin "14") (pinfunction "VCC_14") (pintype "unspecified"))
      (node (ref "AD2") (pin "14") (pinfunction "VCC_14") (pintype "unspecified"))
      (node (ref "AD3") (pin "16") (pinfunction "VCC_16") (pintype "unspecified"))
      (node (ref "CC") (pin "16") (pinfunction "VCC_16") (pintype "bidirectional"))
      (node (ref "CPU") (pin "2") (pinfunction "RDY_2") (pintype "unspecified"))
      (node (ref "CPU") (pin "36") (pinfunction "BE_36") (pintype "input"))
      (node (ref "CPU") (pin "6") (pinfunction "NMIB_6") (pintype "input"))
      (node (ref "CPU") (pin "8") (pinfunction "VDD_8") (pintype "passive"))
      (node (ref "CROM") (pin "27") (pinfunction "WE_27") (pintype "unspecified"))
      (node (ref "CROM") (pin "28") (pinfunction "VCC_28") (pintype "unspecified"))
      (node (ref "DC1") (pin "1") (pinfunction "1_1") (pintype "unspecified"))
      (node (ref "HC") (pin "16") (pinfunction "VCC_16") (pintype "unspecified"))
      (node (ref "HCI") (pin "14") (pinfunction "VCC_14") (pintype "unspecified"))
      (node (ref "HCT") (pin "14") (pinfunction "VCC_14") (pintype "unspecified"))
      (node (ref "K1") (pin "14") (pinfunction "VCC_14") (pintype "unspecified"))
      (node (ref "K2") (pin "10") (pinfunction "SRCLR#_10") (pintype "unspecified"))
      (node (ref "K2") (pin "16") (pinfunction "VCC_16") (pintype "unspecified"))
      (node (ref "K3") (pin "10") (pinfunction "SRCLR#_10") (pintype "unspecified"))
      (node (ref "K3") (pin "16") (pinfunction "VCC_16") (pintype "unspecified"))
      (node (ref "KEYBOARD") (pin "4") (pinfunction "VCC5_4") (pintype "passive"))
      (node (ref "PXS") (pin "16") (pinfunction "VCC_16") (pintype "unspecified"))
      (node (ref "R1") (pin "1") (pinfunction "1_1") (pintype "unspecified"))
      (node (ref "R9") (pin "2") (pinfunction "2_2") (pintype "unspecified"))
      (node (ref "RAM") (pin "28") (pinfunction "VCC_28") (pintype "unspecified"))
      (node (ref "RC") (pin "16") (pinfunction "VCC_16") (pintype "bidirectional"))
      (node (ref "ROM") (pin "27") (pinfunction "/WE_27") (pintype "input"))
      (node (ref "ROM") (pin "28") (pinfunction "VCC_28") (pintype "passive"))
      (node (ref "T8") (pin "14") (pinfunction "VCC_14") (pintype "unspecified"))
      (node (ref "VA") (pin "14") (pinfunction "VCC_14") (pintype "unspecified"))
      (node (ref "VC") (pin "16") (pinfunction "VCC_16") (pintype "unspecified"))
      (node (ref "VCC") (pin "1") (pinfunction "1_1") (pintype "input"))
      (node (ref "VCI") (pin "14") (pinfunction "VCC_14") (pintype "unspecified"))
      (node (ref "VCT") (pin "14") (pinfunction "VCC_14") (pintype "unspecified"))
      (node (ref "VIA") (pin "20") (pinfunction "VCC_20") (pintype "unspecified"))
      (node (ref "VIA2") (pin "20") (pinfunction "VCC_20") (pintype "unspecified"))
      (node (ref "VRAM") (pin "2") (pinfunction "R/!WL_2") (pintype "unspecified"))
      (node (ref "VRAM") (pin "48") (pinfunction "Vcc_48") (pintype "unspecified"))
      (node (ref "X2") (pin "14") (pinfunction "+V_14") (pintype "unspecified"))
    )
    (net (code "173") (name "Vsync") (class "Default")
      (node (ref "DSUB2") (pin "14") (pinfunction "VSYNC_14") (pintype "unspecified"))
      (node (ref "VCT") (pin "10") (pinfunction "3B_10") (pintype "unspecified"))
      (node (ref "VCT") (pin "11") (pinfunction "4Y_11") (pintype "unspecified"))
      (node (ref "VS") (pin "1") (pinfunction "Vs_1") (pintype "input"))
    )
    (net (code "174") (name "px") (class "Default")
      (node (ref "PXS") (pin "9") (pinfunction "QH_9") (pintype "unspecified"))
      (node (ref "VA") (pin "12") (pinfunction "4A_12") (pintype "unspecified"))
    )
    (net (code "175") (name "pxclk") (class "Default")
      (node (ref "HC") (pin "10") (pinfunction "CLK_10") (pintype "unspecified"))
      (node (ref "PXS") (pin "2") (pinfunction "CLK_2") (pintype "unspecified"))
      (node (ref "X2") (pin "8") (pinfunction "OUT_8") (pintype "unspecified"))
    )
    (net (code "176") (name "rgb") (class "Default")
      (node (ref "DSUB2") (pin "1") (pinfunction "R_1") (pintype "unspecified"))
      (node (ref "DSUB2") (pin "2") (pinfunction "G_2") (pintype "unspecified"))
      (node (ref "DSUB2") (pin "3") (pinfunction "B_3") (pintype "unspecified"))
      (node (ref "R8") (pin "2") (pinfunction "2_2") (pintype "unspecified"))
      (node (ref "VA") (pin "8") (pinfunction "3Y_8") (pintype "unspecified"))
    )
    (net (code "177") (name "sh{slash}ld") (class "Default")
      (node (ref "PXS") (pin "1") (pinfunction "SH/LD#_1") (pintype "unspecified"))
      (node (ref "T8") (pin "8") (pinfunction "Y#_8") (pintype "unspecified"))
    )
    (net (code "178") (name "unconnected-(400-NC-Pad9)") (class "Default")
      (node (ref "400") (pin "9") (pinfunction "NC_9") (pintype "unspecified+no_connect"))
    )
    (net (code "179") (name "unconnected-(400-NC-Pad10)") (class "Default")
      (node (ref "400") (pin "10") (pinfunction "NC_10") (pintype "unspecified+no_connect"))
    )
    (net (code "180") (name "unconnected-(400-NC-Pad13)") (class "Default")
      (node (ref "400") (pin "13") (pinfunction "NC_13") (pintype "unspecified+no_connect"))
    )
    (net (code "181") (name "unconnected-(420-NC-Pad9)") (class "Default")
      (node (ref "420") (pin "9") (pinfunction "NC_9") (pintype "unspecified+no_connect"))
    )
    (net (code "182") (name "unconnected-(420-NC-Pad10)") (class "Default")
      (node (ref "420") (pin "10") (pinfunction "NC_10") (pintype "unspecified+no_connect"))
    )
    (net (code "183") (name "unconnected-(420-NC-Pad13)") (class "Default")
      (node (ref "420") (pin "13") (pinfunction "NC_13") (pintype "unspecified+no_connect"))
    )
    (net (code "184") (name "unconnected-(484-NC-Pad9)") (class "Default")
      (node (ref "484") (pin "9") (pinfunction "NC_9") (pintype "unspecified+no_connect"))
    )
    (net (code "185") (name "unconnected-(484-NC-Pad10)") (class "Default")
      (node (ref "484") (pin "10") (pinfunction "NC_10") (pintype "unspecified+no_connect"))
    )
    (net (code "186") (name "unconnected-(484-NC-Pad13)") (class "Default")
      (node (ref "484") (pin "13") (pinfunction "NC_13") (pintype "unspecified+no_connect"))
    )
    (net (code "187") (name "unconnected-(600-NC-Pad9)") (class "Default")
      (node (ref "600") (pin "9") (pinfunction "NC_9") (pintype "unspecified+no_connect"))
    )
    (net (code "188") (name "unconnected-(600-NC-Pad10)") (class "Default")
      (node (ref "600") (pin "10") (pinfunction "NC_10") (pintype "unspecified+no_connect"))
    )
    (net (code "189") (name "unconnected-(600-NC-Pad13)") (class "Default")
      (node (ref "600") (pin "13") (pinfunction "NC_13") (pintype "unspecified+no_connect"))
    )
    (net (code "190") (name "unconnected-(601-NC-Pad9)") (class "Default")
      (node (ref "601") (pin "9") (pinfunction "NC_9") (pintype "unspecified+no_connect"))
    )
    (net (code "191") (name "unconnected-(601-NC-Pad10)") (class "Default")
      (node (ref "601") (pin "10") (pinfunction "NC_10") (pintype "unspecified+no_connect"))
    )
    (net (code "192") (name "unconnected-(601-NC-Pad13)") (class "Default")
      (node (ref "601") (pin "13") (pinfunction "NC_13") (pintype "unspecified+no_connect"))
    )
    (net (code "193") (name "unconnected-(605-NC-Pad9)") (class "Default")
      (node (ref "605") (pin "9") (pinfunction "NC_9") (pintype "unspecified+no_connect"))
    )
    (net (code "194") (name "unconnected-(605-NC-Pad10)") (class "Default")
      (node (ref "605") (pin "10") (pinfunction "NC_10") (pintype "unspecified+no_connect"))
    )
    (net (code "195") (name "unconnected-(605-NC-Pad13)") (class "Default")
      (node (ref "605") (pin "13") (pinfunction "NC_13") (pintype "unspecified+no_connect"))
    )
    (net (code "196") (name "unconnected-(628-NC-Pad9)") (class "Default")
      (node (ref "628") (pin "9") (pinfunction "NC_9") (pintype "unspecified+no_connect"))
    )
    (net (code "197") (name "unconnected-(628-NC-Pad10)") (class "Default")
      (node (ref "628") (pin "10") (pinfunction "NC_10") (pintype "unspecified+no_connect"))
    )
    (net (code "198") (name "unconnected-(628-NC-Pad13)") (class "Default")
      (node (ref "628") (pin "13") (pinfunction "NC_13") (pintype "unspecified+no_connect"))
    )
    (net (code "199") (name "unconnected-(ACIA--IRQ-Pad26)") (class "Default")
      (node (ref "ACIA") (pin "26") (pinfunction "-IRQ_26") (pintype "unspecified+no_connect"))
    )
    (net (code "200") (name "unconnected-(ACIA-RxC-Pad5)") (class "Default")
      (node (ref "ACIA") (pin "5") (pinfunction "RxC_5") (pintype "unspecified+no_connect"))
    )
    (net (code "201") (name "unconnected-(AD2-3A-Pad9)") (class "Default")
      (node (ref "AD2") (pin "9") (pinfunction "3A_9") (pintype "unspecified+no_connect"))
    )
    (net (code "202") (name "unconnected-(AD2-3B-Pad10)") (class "Default")
      (node (ref "AD2") (pin "10") (pinfunction "3B_10") (pintype "unspecified+no_connect"))
    )
    (net (code "203") (name "unconnected-(AD2-3Y-Pad8)") (class "Default")
      (node (ref "AD2") (pin "8") (pinfunction "3Y_8") (pintype "unspecified+no_connect"))
    )
    (net (code "204") (name "unconnected-(AD3-{slash}Y0-Pad1)") (class "Default")
      (node (ref "AD3") (pin "1") (pinfunction "/Y0_1") (pintype "unspecified+no_connect"))
    )
    (net (code "205") (name "unconnected-(AD3-{slash}Y1-Pad2)") (class "Default")
      (node (ref "AD3") (pin "2") (pinfunction "/Y1_2") (pintype "unspecified+no_connect"))
    )
    (net (code "206") (name "unconnected-(AD3-{slash}Y2-Pad3)") (class "Default")
      (node (ref "AD3") (pin "3") (pinfunction "/Y2_3") (pintype "unspecified+no_connect"))
    )
    (net (code "207") (name "unconnected-(AD3-{slash}Y4-Pad5)") (class "Default")
      (node (ref "AD3") (pin "5") (pinfunction "/Y4_5") (pintype "unspecified+no_connect"))
    )
    (net (code "208") (name "unconnected-(AD3-{slash}Y5-Pad6)") (class "Default")
      (node (ref "AD3") (pin "6") (pinfunction "/Y5_6") (pintype "unspecified+no_connect"))
    )
    (net (code "209") (name "unconnected-(AD3-{slash}Y6-Pad7)") (class "Default")
      (node (ref "AD3") (pin "7") (pinfunction "/Y6_7") (pintype "unspecified+no_connect"))
    )
    (net (code "210") (name "unconnected-(AD3-{slash}Y7-Pad9)") (class "Default")
      (node (ref "AD3") (pin "9") (pinfunction "/Y7_9") (pintype "unspecified+no_connect"))
    )
    (net (code "211") (name "unconnected-(AD3-{slash}Y8-Pad10)") (class "Default")
      (node (ref "AD3") (pin "10") (pinfunction "/Y8_10") (pintype "unspecified+no_connect"))
    )
    (net (code "212") (name "unconnected-(AD3-{slash}Y9-Pad11)") (class "Default")
      (node (ref "AD3") (pin "11") (pinfunction "/Y9_11") (pintype "unspecified+no_connect"))
    )
    (net (code "213") (name "unconnected-(CC-QG-Pad4)") (class "Default")
      (node (ref "CC") (pin "4") (pinfunction "QG_4") (pintype "bidirectional"))
    )
    (net (code "214") (name "unconnected-(CC-QH-Pad13)") (class "Default")
      (node (ref "CC") (pin "13") (pinfunction "QH_13") (pintype "bidirectional"))
    )
    (net (code "215") (name "unconnected-(CC-QI-Pad12)") (class "Default")
      (node (ref "CC") (pin "12") (pinfunction "QI_12") (pintype "bidirectional"))
    )
    (net (code "216") (name "unconnected-(CC-QJ-Pad14)") (class "Default")
      (node (ref "CC") (pin "14") (pinfunction "QJ_14") (pintype "bidirectional"))
    )
    (net (code "217") (name "unconnected-(CC-QK-Pad15)") (class "Default")
      (node (ref "CC") (pin "15") (pinfunction "QK_15") (pintype "bidirectional"))
    )
    (net (code "218") (name "unconnected-(CC-QL-Pad1)") (class "Default")
      (node (ref "CC") (pin "1") (pinfunction "QL_1") (pintype "bidirectional"))
    )
    (net (code "219") (name "unconnected-(CPU-MLB-Pad5)") (class "Default")
      (node (ref "CPU") (pin "5") (pinfunction "MLB_5") (pintype "output+no_connect"))
    )
    (net (code "220") (name "unconnected-(CPU-NC-Pad35)") (class "Default")
      (node (ref "CPU") (pin "35") (pinfunction "NC_35") (pintype "unspecified+no_connect"))
    )
    (net (code "221") (name "unconnected-(CPU-PHI1-Pad3)") (class "Default")
      (node (ref "CPU") (pin "3") (pinfunction "PHI1_3") (pintype "output+no_connect"))
    )
    (net (code "222") (name "unconnected-(CPU-PHI2-Pad39)") (class "Default")
      (node (ref "CPU") (pin "39") (pinfunction "PHI2_39") (pintype "output+no_connect"))
    )
    (net (code "223") (name "unconnected-(CPU-SOB-Pad38)") (class "Default")
      (node (ref "CPU") (pin "38") (pinfunction "SOB_38") (pintype "input+no_connect"))
    )
    (net (code "224") (name "unconnected-(CPU-SYNC-Pad7)") (class "Default")
      (node (ref "CPU") (pin "7") (pinfunction "SYNC_7") (pintype "output+no_connect"))
    )
    (net (code "225") (name "unconnected-(CPU-VPB-Pad1)") (class "Default")
      (node (ref "CPU") (pin "1") (pinfunction "VPB_1") (pintype "output+no_connect"))
    )
    (net (code "226") (name "unconnected-(CROM-NC0-Pad1)") (class "Default")
      (node (ref "CROM") (pin "1") (pinfunction "NC0_1") (pintype "unspecified+no_connect"))
    )
    (net (code "227") (name "unconnected-(CROM-NC1-Pad26)") (class "Default")
      (node (ref "CROM") (pin "26") (pinfunction "NC1_26") (pintype "unspecified+no_connect"))
    )
    (net (code "228") (name "unconnected-(DSUB2-B_RTN-Pad8)") (class "Default")
      (node (ref "DSUB2") (pin "8") (pinfunction "B_RTN_8") (pintype "unspecified+no_connect"))
    )
    (net (code "229") (name "unconnected-(DSUB2-G_RTN-Pad7)") (class "Default")
      (node (ref "DSUB2") (pin "7") (pinfunction "G_RTN_7") (pintype "unspecified+no_connect"))
    )
    (net (code "230") (name "unconnected-(DSUB2-ID0{slash}RES-Pad11)") (class "Default")
      (node (ref "DSUB2") (pin "11") (pinfunction "ID0/RES_11") (pintype "unspecified+no_connect"))
    )
    (net (code "231") (name "unconnected-(DSUB2-ID1{slash}SDA-Pad12)") (class "Default")
      (node (ref "DSUB2") (pin "12") (pinfunction "ID1/SDA_12") (pintype "unspecified+no_connect"))
    )
    (net (code "232") (name "unconnected-(DSUB2-ID2{slash}RES-Pad4)") (class "Default")
      (node (ref "DSUB2") (pin "4") (pinfunction "ID2/RES_4") (pintype "unspecified+no_connect"))
    )
    (net (code "233") (name "unconnected-(DSUB2-ID3{slash}SCL-Pad15)") (class "Default")
      (node (ref "DSUB2") (pin "15") (pinfunction "ID3/SCL_15") (pintype "unspecified+no_connect"))
    )
    (net (code "234") (name "unconnected-(DSUB2-KEY{slash}PWR-Pad9)") (class "Default")
      (node (ref "DSUB2") (pin "9") (pinfunction "KEY/PWR_9") (pintype "unspecified+no_connect"))
    )
    (net (code "235") (name "unconnected-(DSUB2-R_RTN-Pad6)") (class "Default")
      (node (ref "DSUB2") (pin "6") (pinfunction "R_RTN_6") (pintype "unspecified+no_connect"))
    )
    (net (code "236") (name "unconnected-(HC-QK-Pad15)") (class "Default")
      (node (ref "HC") (pin "15") (pinfunction "QK_15") (pintype "unspecified+no_connect"))
    )
    (net (code "237") (name "unconnected-(HC-QL-Pad1)") (class "Default")
      (node (ref "HC") (pin "1") (pinfunction "QL_1") (pintype "unspecified+no_connect"))
    )
    (net (code "238") (name "unconnected-(K1-3Y-Pad6)") (class "Default")
      (node (ref "K1") (pin "6") (pinfunction "3Y_6") (pintype "unspecified+no_connect"))
    )
    (net (code "239") (name "unconnected-(K1-5Y-Pad10)") (class "Default")
      (node (ref "K1") (pin "10") (pinfunction "5Y_10") (pintype "unspecified+no_connect"))
    )
    (net (code "240") (name "unconnected-(K1-6Y-Pad12)") (class "Default")
      (node (ref "K1") (pin "12") (pinfunction "6Y_12") (pintype "unspecified+no_connect"))
    )
    (net (code "241") (name "unconnected-(K2-QA-Pad15)") (class "Default")
      (node (ref "K2") (pin "15") (pinfunction "QA_15") (pintype "unspecified+no_connect"))
    )
    (net (code "242") (name "unconnected-(K2-QB-Pad1)") (class "Default")
      (node (ref "K2") (pin "1") (pinfunction "QB_1") (pintype "unspecified+no_connect"))
    )
    (net (code "243") (name "unconnected-(K3-QC-Pad2)") (class "Default")
      (node (ref "K3") (pin "2") (pinfunction "QC_2") (pintype "unspecified+no_connect"))
    )
    (net (code "244") (name "unconnected-(K3-QD-Pad3)") (class "Default")
      (node (ref "K3") (pin "3") (pinfunction "QD_3") (pintype "unspecified+no_connect"))
    )
    (net (code "245") (name "unconnected-(K3-QE-Pad4)") (class "Default")
      (node (ref "K3") (pin "4") (pinfunction "QE_4") (pintype "unspecified+no_connect"))
    )
    (net (code "246") (name "unconnected-(K3-QF-Pad5)") (class "Default")
      (node (ref "K3") (pin "5") (pinfunction "QF_5") (pintype "unspecified+no_connect"))
    )
    (net (code "247") (name "unconnected-(K3-QG-Pad6)") (class "Default")
      (node (ref "K3") (pin "6") (pinfunction "QG_6") (pintype "unspecified+no_connect"))
    )
    (net (code "248") (name "unconnected-(K3-QH&apos;-Pad9)") (class "Default")
      (node (ref "K3") (pin "9") (pinfunction "QH&apos;_9") (pintype "unspecified+no_connect"))
    )
    (net (code "249") (name "unconnected-(K3-QH-Pad7)") (class "Default")
      (node (ref "K3") (pin "7") (pinfunction "QH_7") (pintype "unspecified+no_connect"))
    )
    (net (code "250") (name "unconnected-(KEYBOARD-NI-Pad2)") (class "Default")
      (node (ref "KEYBOARD") (pin "2") (pinfunction "NI_2") (pintype "input+no_connect"))
    )
    (net (code "251") (name "unconnected-(KEYBOARD-NI-Pad6)") (class "Default")
      (node (ref "KEYBOARD") (pin "6") (pinfunction "NI_6") (pintype "input+no_connect"))
    )
    (net (code "252") (name "unconnected-(KEYBOARD-SH1-Pad7)") (class "Default")
      (node (ref "KEYBOARD") (pin "7") (pinfunction "SH1_7") (pintype "passive+no_connect"))
    )
    (net (code "253") (name "unconnected-(KEYBOARD-SH2-Pad8)") (class "Default")
      (node (ref "KEYBOARD") (pin "8") (pinfunction "SH2_8") (pintype "passive+no_connect"))
    )
    (net (code "254") (name "unconnected-(KEYBOARD-SH3-Pad9)") (class "Default")
      (node (ref "KEYBOARD") (pin "9") (pinfunction "SH3_9") (pintype "passive+no_connect"))
    )
    (net (code "255") (name "unconnected-(PXS-QH#-Pad7)") (class "Default")
      (node (ref "PXS") (pin "7") (pinfunction "QH#_7") (pintype "unspecified+no_connect"))
    )
    (net (code "256") (name "unconnected-(PXS-SER-Pad10)") (class "Default")
      (node (ref "PXS") (pin "10") (pinfunction "SER_10") (pintype "unspecified+no_connect"))
    )
    (net (code "257") (name "unconnected-(RC-QG-Pad4)") (class "Default")
      (node (ref "RC") (pin "4") (pinfunction "QG_4") (pintype "bidirectional"))
    )
    (net (code "258") (name "unconnected-(RC-QH-Pad13)") (class "Default")
      (node (ref "RC") (pin "13") (pinfunction "QH_13") (pintype "bidirectional"))
    )
    (net (code "259") (name "unconnected-(RC-QI-Pad12)") (class "Default")
      (node (ref "RC") (pin "12") (pinfunction "QI_12") (pintype "bidirectional"))
    )
    (net (code "260") (name "unconnected-(RC-QJ-Pad14)") (class "Default")
      (node (ref "RC") (pin "14") (pinfunction "QJ_14") (pintype "bidirectional"))
    )
    (net (code "261") (name "unconnected-(RC-QK-Pad15)") (class "Default")
      (node (ref "RC") (pin "15") (pinfunction "QK_15") (pintype "bidirectional"))
    )
    (net (code "262") (name "unconnected-(RC-QL-Pad1)") (class "Default")
      (node (ref "RC") (pin "1") (pinfunction "QL_1") (pintype "bidirectional"))
    )
    (net (code "263") (name "unconnected-(SW1-Pad2)") (class "Default")
      (node (ref "SW1") (pin "2") (pinfunction "2_2") (pintype "unspecified+no_connect"))
    )
    (net (code "264") (name "unconnected-(T8-NC-Pad9)") (class "Default")
      (node (ref "T8") (pin "9") (pinfunction "NC_9") (pintype "unspecified+no_connect"))
    )
    (net (code "265") (name "unconnected-(T8-NC-Pad10)") (class "Default")
      (node (ref "T8") (pin "10") (pinfunction "NC_10") (pintype "unspecified+no_connect"))
    )
    (net (code "266") (name "unconnected-(T8-NC-Pad13)") (class "Default")
      (node (ref "T8") (pin "13") (pinfunction "NC_13") (pintype "unspecified+no_connect"))
    )
    (net (code "267") (name "unconnected-(VC-QH-Pad13)") (class "Default")
      (node (ref "VC") (pin "13") (pinfunction "QH_13") (pintype "unspecified+no_connect"))
    )
    (net (code "268") (name "unconnected-(VC-QI-Pad12)") (class "Default")
      (node (ref "VC") (pin "12") (pinfunction "QI_12") (pintype "unspecified+no_connect"))
    )
    (net (code "269") (name "unconnected-(VC-QK-Pad15)") (class "Default")
      (node (ref "VC") (pin "15") (pinfunction "QK_15") (pintype "unspecified+no_connect"))
    )
    (net (code "270") (name "unconnected-(VC-QL-Pad1)") (class "Default")
      (node (ref "VC") (pin "1") (pinfunction "QL_1") (pintype "unspecified+no_connect"))
    )
    (net (code "271") (name "unconnected-(VIA-CA2-Pad39)") (class "Default")
      (node (ref "VIA") (pin "39") (pinfunction "CA2_39") (pintype "unspecified+no_connect"))
    )
    (net (code "272") (name "unconnected-(VIA-CB1-Pad18)") (class "Default")
      (node (ref "VIA") (pin "18") (pinfunction "CB1_18") (pintype "unspecified+no_connect"))
    )
    (net (code "273") (name "unconnected-(VIA-CB2-Pad19)") (class "Default")
      (node (ref "VIA") (pin "19") (pinfunction "CB2_19") (pintype "unspecified+no_connect"))
    )
    (net (code "274") (name "unconnected-(VIA2-CA1-Pad40)") (class "Default")
      (node (ref "VIA2") (pin "40") (pinfunction "CA1_40") (pintype "unspecified+no_connect"))
    )
    (net (code "275") (name "unconnected-(VIA2-CA2-Pad39)") (class "Default")
      (node (ref "VIA2") (pin "39") (pinfunction "CA2_39") (pintype "unspecified+no_connect"))
    )
    (net (code "276") (name "unconnected-(VIA2-CB1-Pad18)") (class "Default")
      (node (ref "VIA2") (pin "18") (pinfunction "CB1_18") (pintype "unspecified+no_connect"))
    )
    (net (code "277") (name "unconnected-(VIA2-CB2-Pad19)") (class "Default")
      (node (ref "VIA2") (pin "19") (pinfunction "CB2_19") (pintype "unspecified+no_connect"))
    )
    (net (code "278") (name "unconnected-(VRAM-!BUSYR-Pad45)") (class "Default")
      (node (ref "VRAM") (pin "45") (pinfunction "!BUSYR_45") (pintype "unspecified+no_connect"))
    )
    (net (code "279") (name "unconnected-(X2-NC-Pad1)") (class "Default")
      (node (ref "X2") (pin "1") (pinfunction "NC_1") (pintype "input+no_connect"))
    )
    (net (code "280") (name "v1") (class "Default")
      (node (ref "601") (pin "1") (pinfunction "A_1") (pintype "unspecified"))
      (node (ref "605") (pin "1") (pinfunction "A_1") (pintype "unspecified"))
      (node (ref "CROM") (pin "10") (pinfunction "A0_10") (pintype "unspecified"))
      (node (ref "VC") (pin "9") (pinfunction "QA_9") (pintype "unspecified"))
      (node (ref "VCI") (pin "1") (pinfunction "1A_1") (pintype "unspecified"))
    )
    (net (code "281") (name "v2") (class "Default")
      (node (ref "CROM") (pin "9") (pinfunction "A1_9") (pintype "unspecified"))
      (node (ref "VC") (pin "7") (pinfunction "QB_7") (pintype "unspecified"))
      (node (ref "VCI") (pin "3") (pinfunction "2A_3") (pintype "unspecified"))
    )
    (net (code "282") (name "v3") (class "Default")
      (node (ref "605") (pin "3") (pinfunction "C_3") (pintype "unspecified"))
      (node (ref "628") (pin "3") (pinfunction "C_3") (pintype "unspecified"))
      (node (ref "CROM") (pin "8") (pinfunction "A2_8") (pintype "unspecified"))
      (node (ref "VC") (pin "6") (pinfunction "QC_6") (pintype "unspecified"))
      (node (ref "VCI") (pin "5") (pinfunction "3A_5") (pintype "unspecified"))
    )
    (net (code "283") (name "v4") (class "Default")
      (node (ref "600") (pin "5") (pinfunction "E_5") (pintype "unspecified"))
      (node (ref "601") (pin "4") (pinfunction "D_4") (pintype "unspecified"))
      (node (ref "605") (pin "4") (pinfunction "D_4") (pintype "unspecified"))
      (node (ref "RC") (pin "10") (pinfunction "CLK_10") (pintype "bidirectional"))
      (node (ref "VC") (pin "5") (pinfunction "QD_5") (pintype "unspecified"))
      (node (ref "VCI") (pin "13") (pinfunction "6A_13") (pintype "unspecified"))
    )
  )
)
